# DumbBadgeFusion.net
KiCad netlist of a schematic drawn in EAGLE
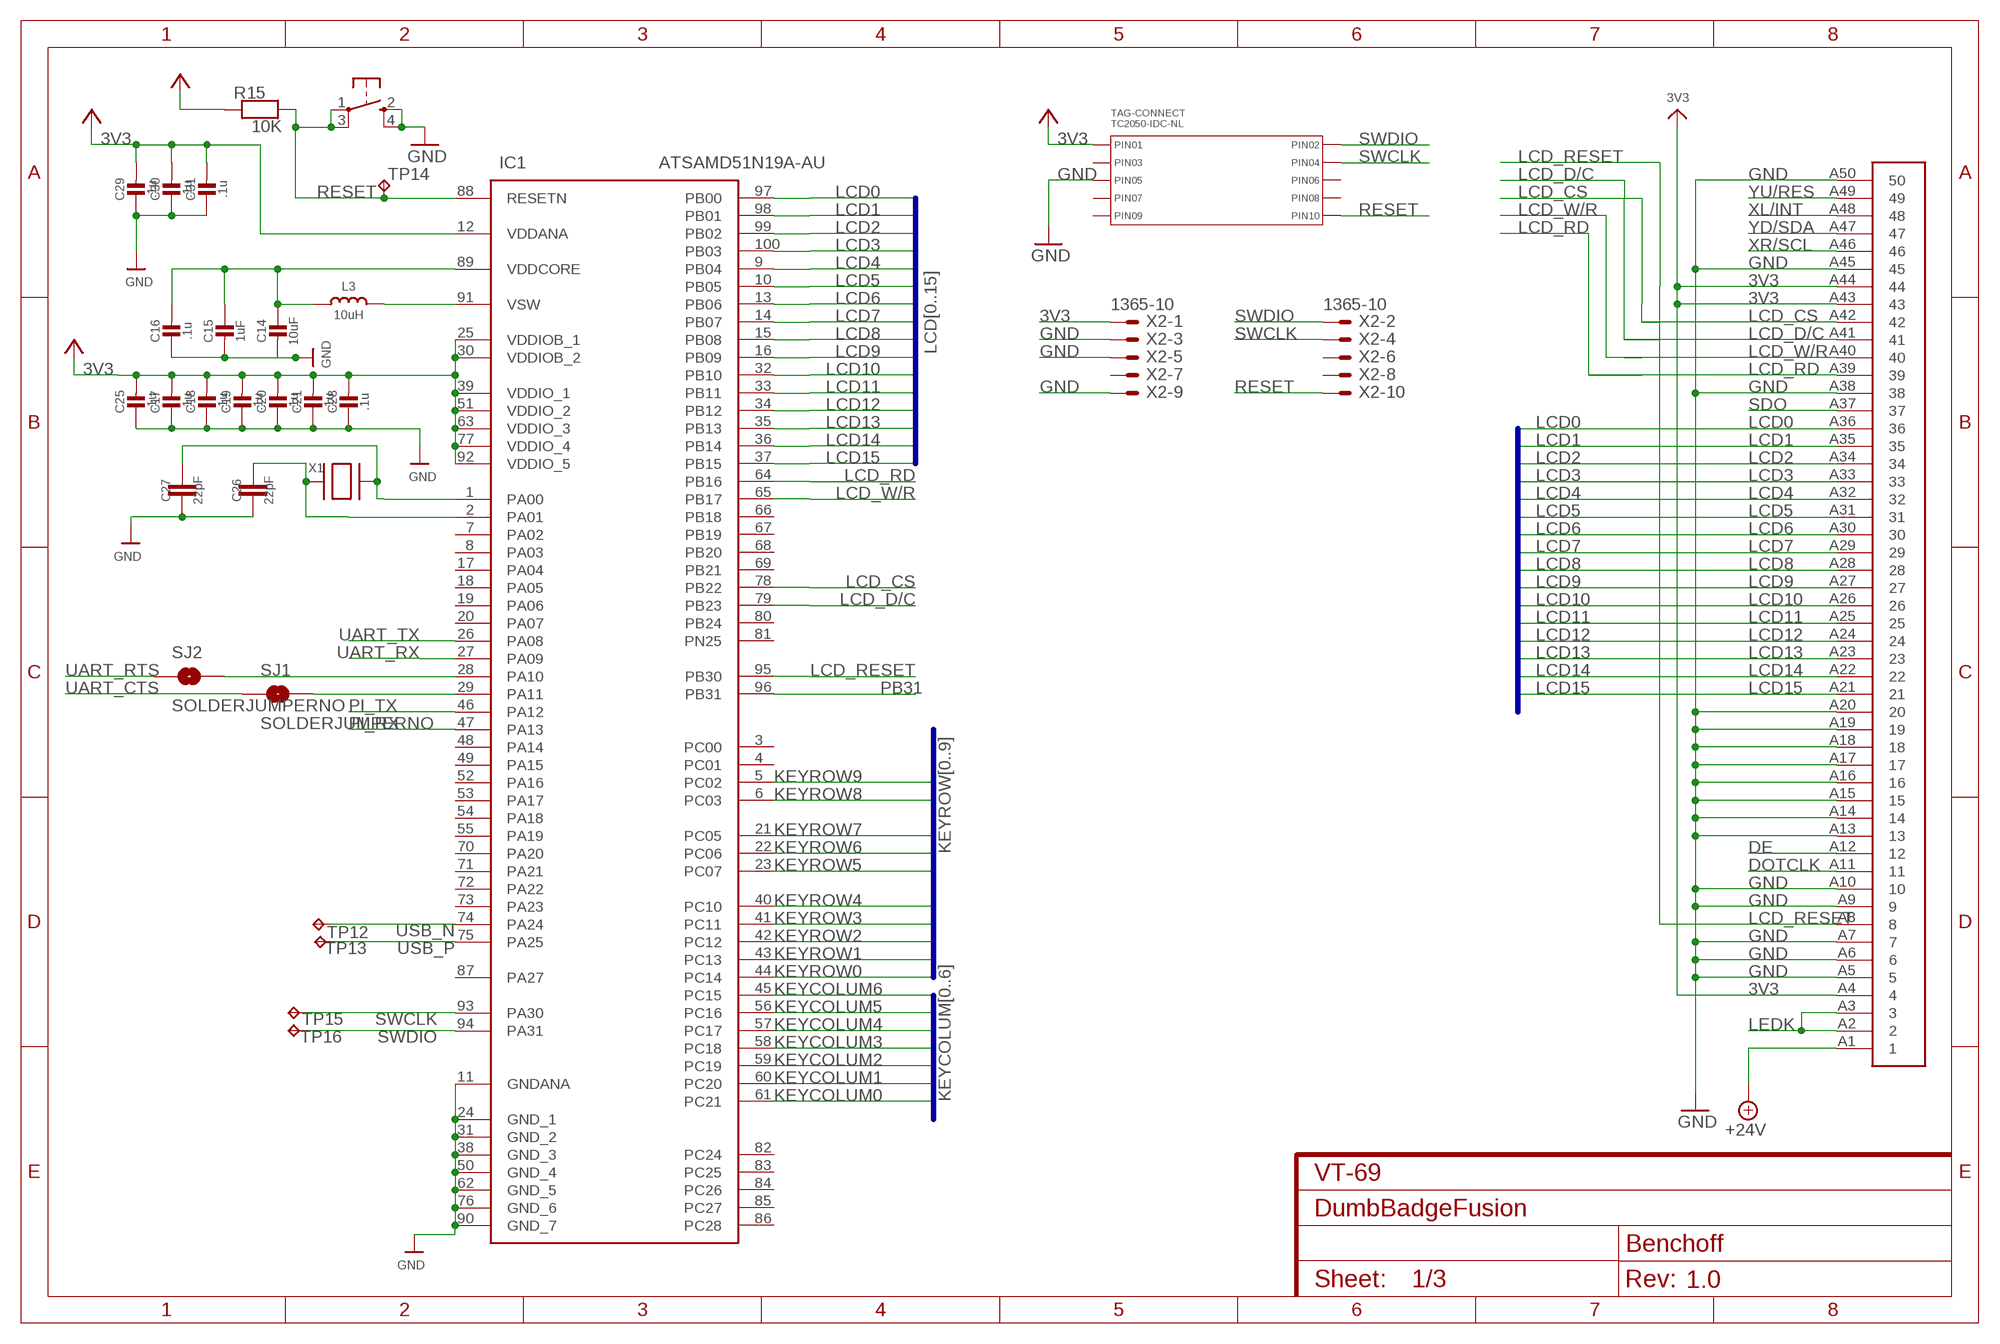
[diagram p0: schematic, sheet 1]
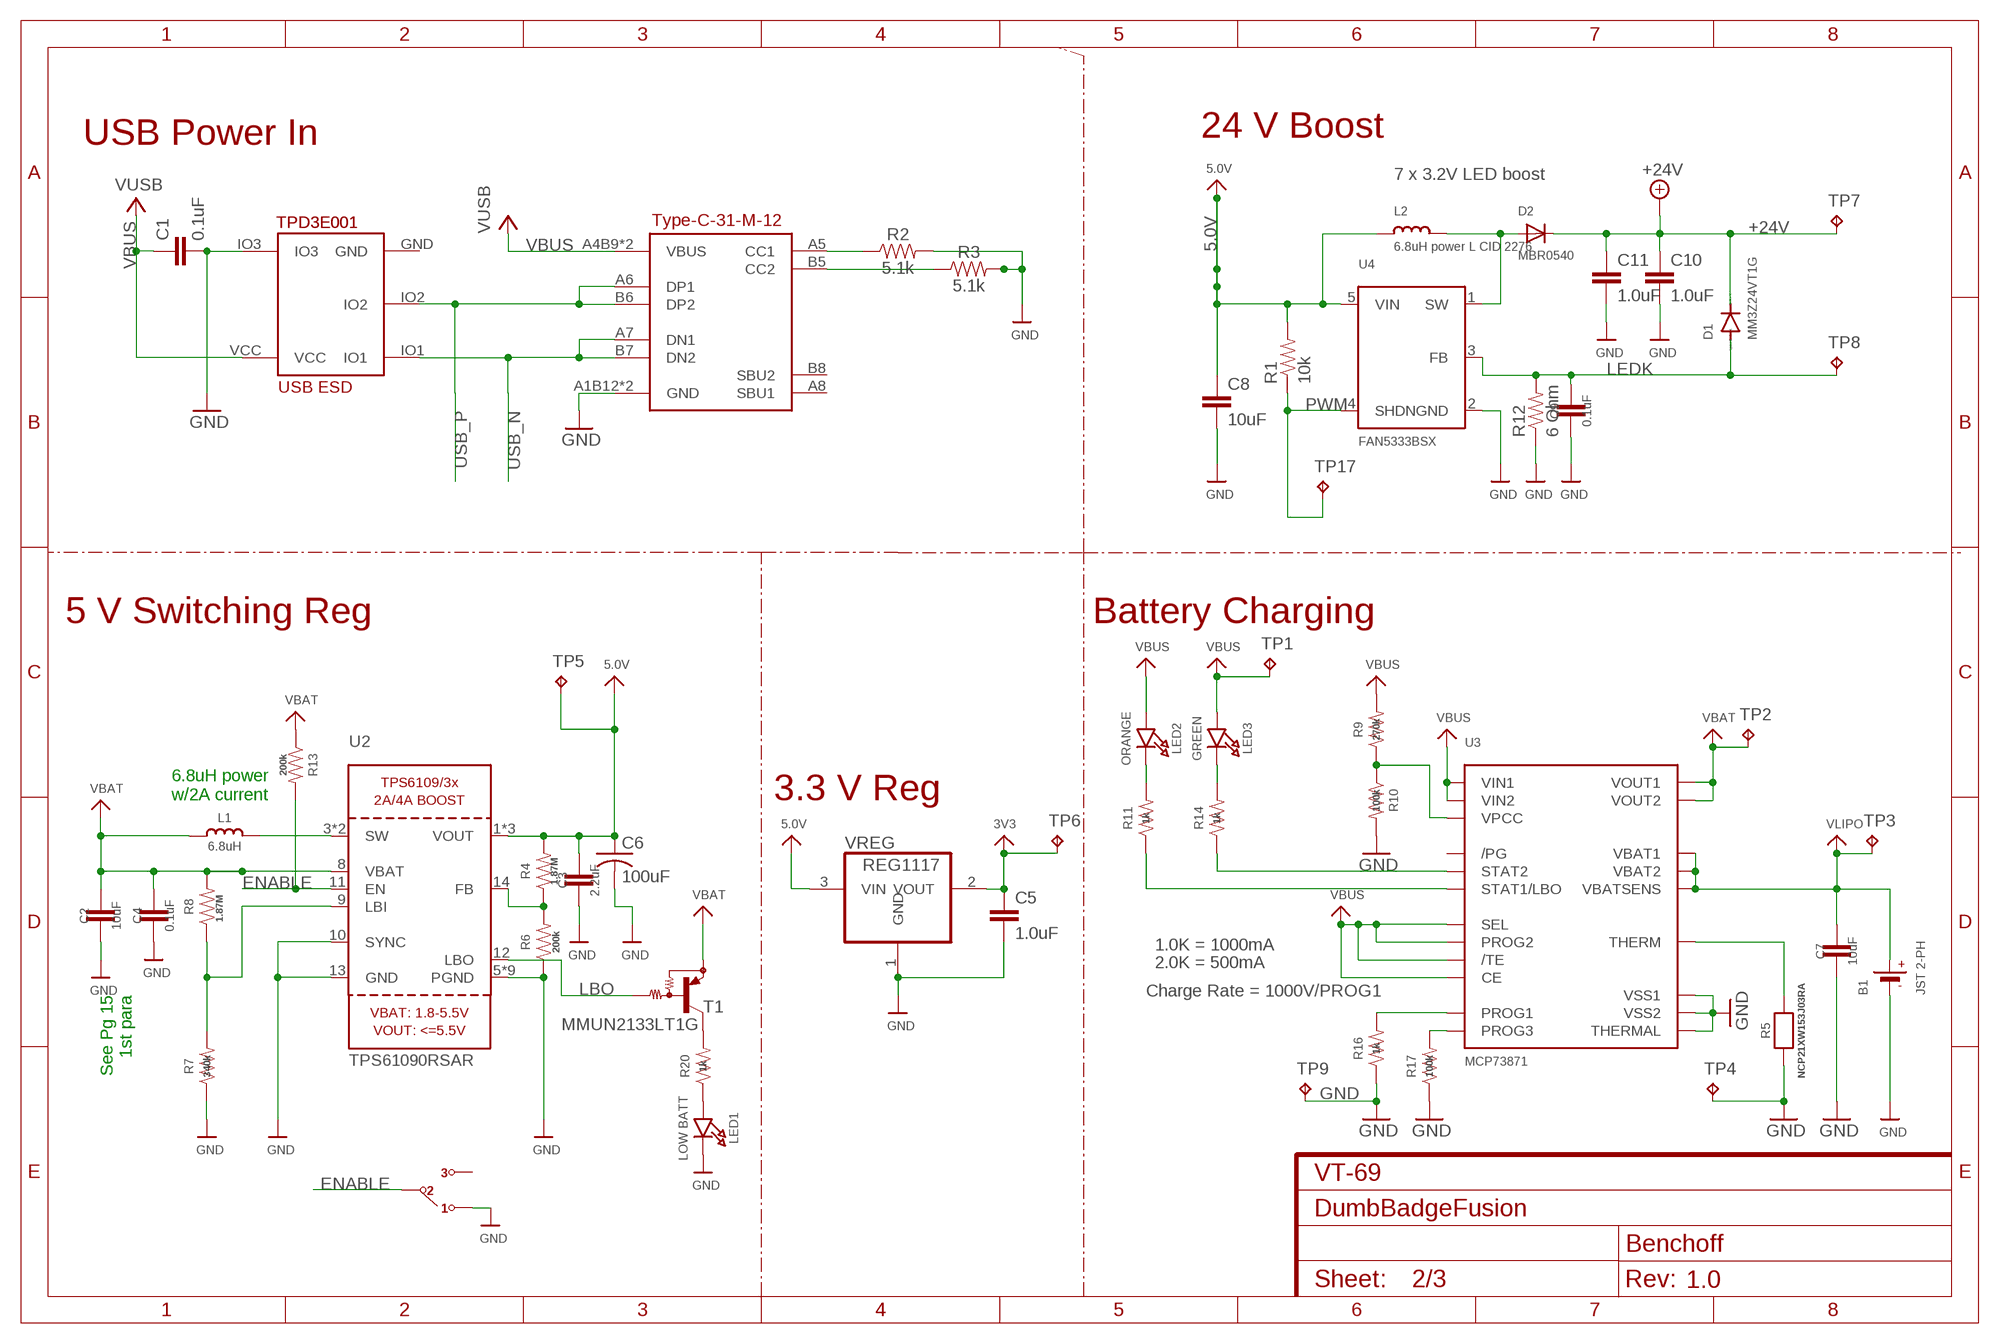
[diagram p1: schematic, sheet 2]
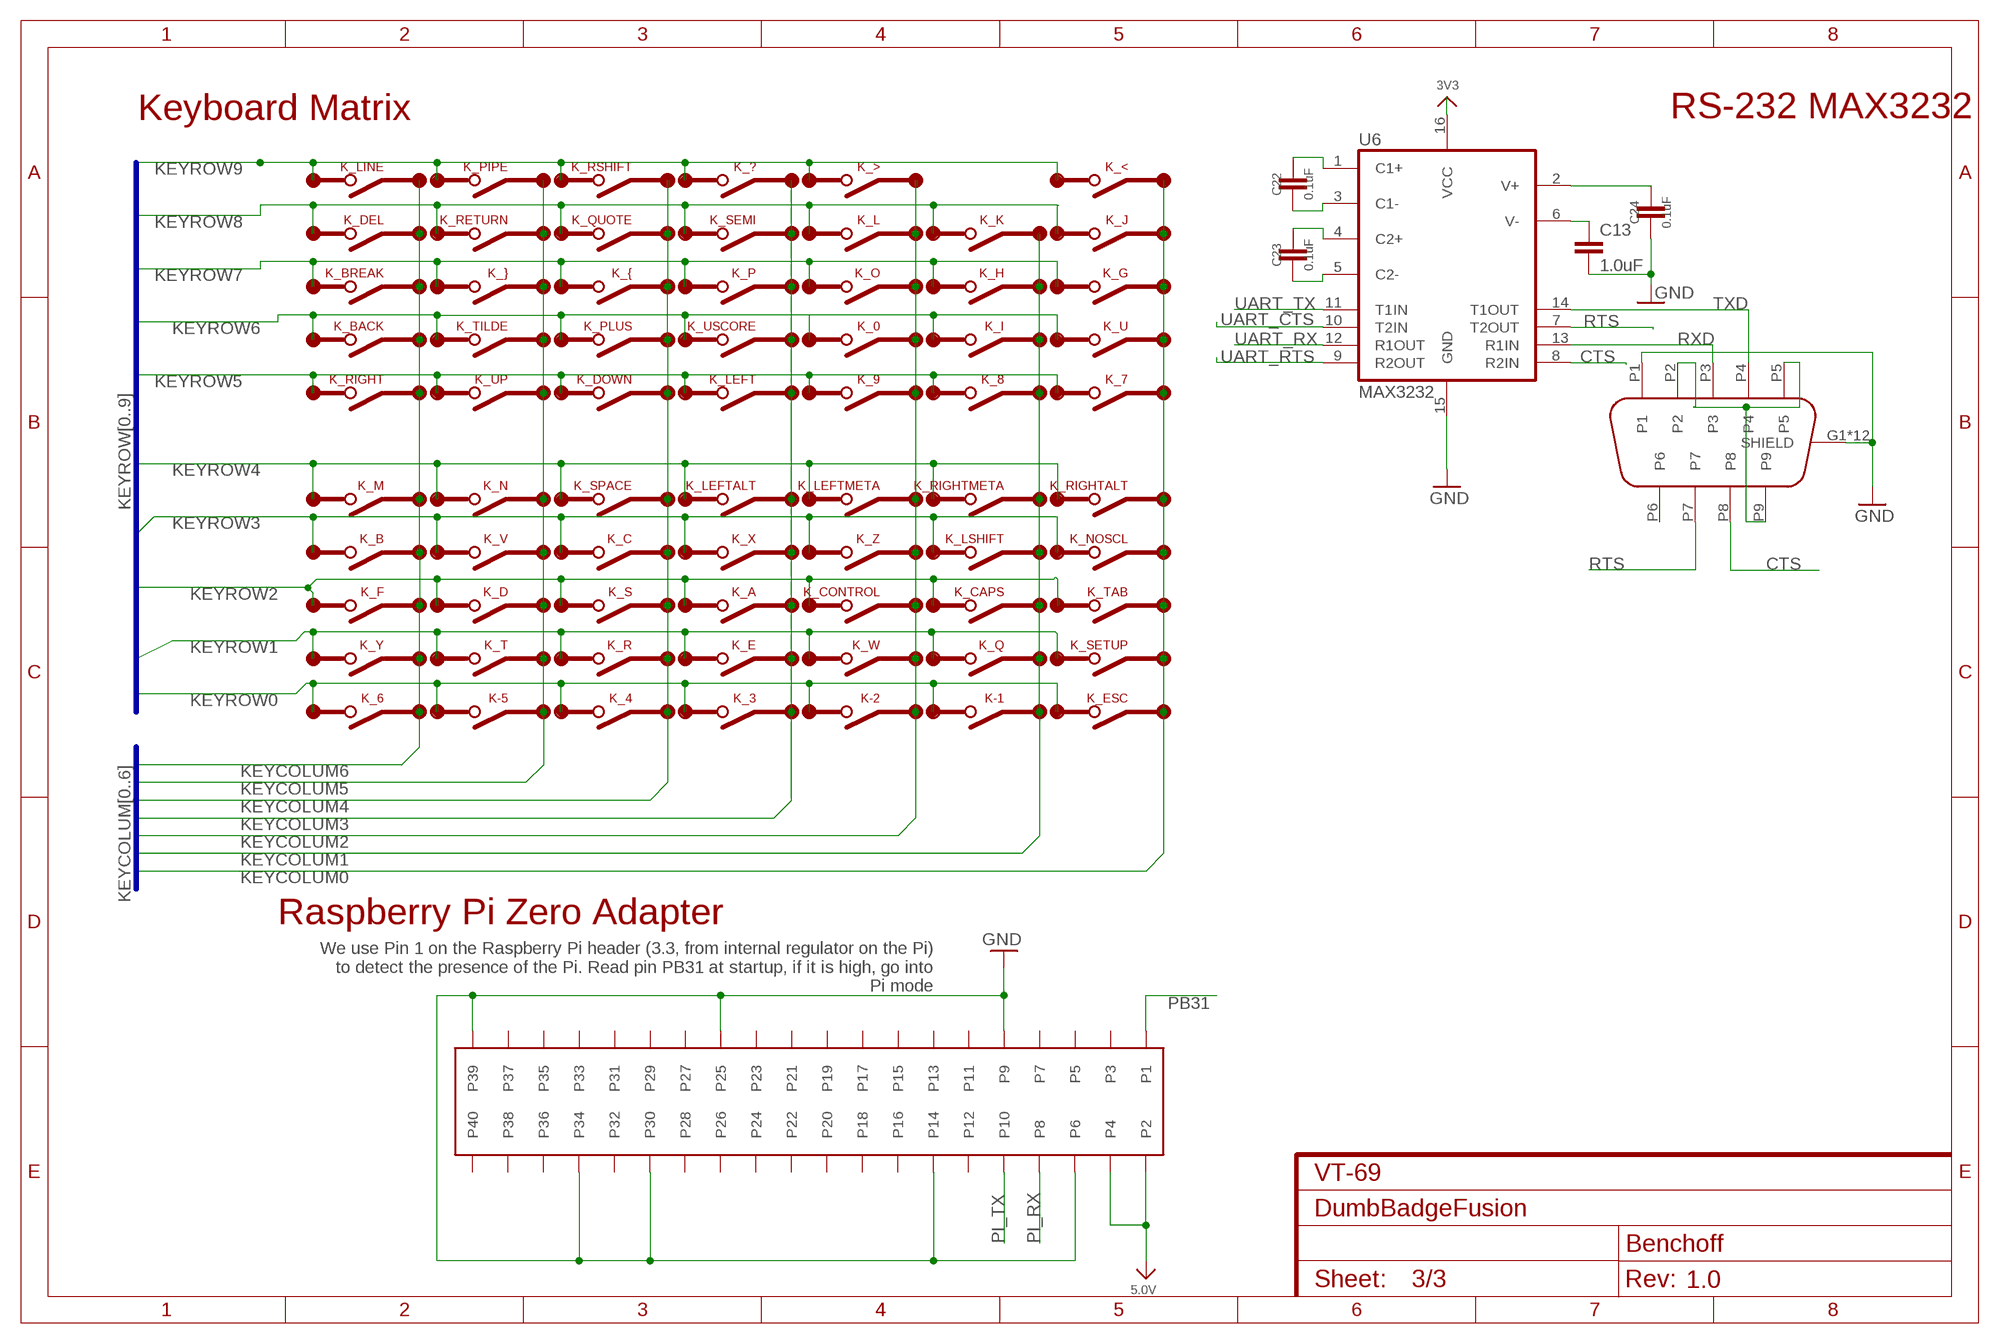
[diagram p2: schematic, sheet 3]

(export (version "E")
  (design (tool "Eeschema 10.0.6"))
  (components
    (comp (ref "C14")
      (value "10uF")
      (footprint "eagle-import:0805-NO")
      (libsource (lib "eagle-import") (part "CAP_CERAMIC0805-NOOUTLINE"))
    )
    (comp (ref "C15")
      (value "1uF")
      (footprint "eagle-import:0603-NO")
      (libsource (lib "eagle-import") (part "CAP_CERAMIC0603_NO"))
    )
    (comp (ref "C16")
      (value ".1u")
      (footprint "eagle-import:0603-NO")
      (libsource (lib "eagle-import") (part "CAP_CERAMIC0603_NO"))
    )
    (comp (ref "C17")
      (value ".1u")
      (footprint "eagle-import:0603-NO")
      (libsource (lib "eagle-import") (part "CAP_CERAMIC0603_NO"))
    )
    (comp (ref "C18")
      (value ".1u")
      (footprint "eagle-import:0603-NO")
      (libsource (lib "eagle-import") (part "CAP_CERAMIC0603_NO"))
    )
    (comp (ref "C19")
      (value ".1u")
      (footprint "eagle-import:0603-NO")
      (libsource (lib "eagle-import") (part "CAP_CERAMIC0603_NO"))
    )
    (comp (ref "C20")
      (value ".1u")
      (footprint "eagle-import:0603-NO")
      (libsource (lib "eagle-import") (part "CAP_CERAMIC0603_NO"))
    )
    (comp (ref "C21")
      (value ".1u")
      (footprint "eagle-import:0603-NO")
      (libsource (lib "eagle-import") (part "CAP_CERAMIC0603_NO"))
    )
    (comp (ref "C25")
      (value ".1u")
      (footprint "eagle-import:0603-NO")
      (libsource (lib "eagle-import") (part "CAP_CERAMIC0603_NO"))
    )
    (comp (ref "C26")
      (value "22pF")
      (footprint "eagle-import:0805")
      (libsource (lib "eagle-import") (part "1.0UF-0805-25V-10%"))
    )
    (comp (ref "C27")
      (value "22pF")
      (footprint "eagle-import:0805")
      (libsource (lib "eagle-import") (part "1.0UF-0805-25V-10%"))
    )
    (comp (ref "C28")
      (value ".1u")
      (footprint "eagle-import:0603-NO")
      (libsource (lib "eagle-import") (part "CAP_CERAMIC0603_NO"))
    )
    (comp (ref "C29")
      (value ".1u")
      (footprint "eagle-import:0603-NO")
      (libsource (lib "eagle-import") (part "CAP_CERAMIC0603_NO"))
    )
    (comp (ref "C30")
      (value ".1u")
      (footprint "eagle-import:0603-NO")
      (libsource (lib "eagle-import") (part "CAP_CERAMIC0603_NO"))
    )
    (comp (ref "C31")
      (value ".1u")
      (footprint "eagle-import:0603-NO")
      (libsource (lib "eagle-import") (part "CAP_CERAMIC0603_NO"))
    )
    (comp (ref "FPC50CONN")
      (value "50PINFPC")
      (footprint "eagle-import:62684-501100ALF")
      (libsource (lib "eagle-import") (part "50PINFPC"))
    )
    (comp (ref "IC1")
      (value "ATSAMD51N19A-AU")
      (footprint "eagle-import:QFP50P1600X1600X120-100N")
      (fields (field (name "MOUSER_PART_NUMBER") "556-ATSAMD51N19AAU"))
      (libsource (lib "eagle-import") (part "ATSAMD51N19A-AU"))
    )
    (comp (ref "L3")
      (value "10uH")
      (footprint "eagle-import:INDUCTOR_1007")
      (libsource (lib "eagle-import") (part "INDUCTOR"))
    )
    (comp (ref "R15")
      (value "10K")
      (footprint "eagle-import:0603-NO")
      (libsource (lib "eagle-import") (part "RESISTOR_0603_NOOUT"))
    )
    (comp (ref "SJ1")
      (value "SOLDERJUMPERNO")
      (footprint "eagle-import:SJ_2S-NO")
      (libsource (lib "eagle-import") (part "SOLDERJUMPERNO"))
    )
    (comp (ref "SJ2")
      (value "SOLDERJUMPERNO")
      (footprint "eagle-import:SJ_2S-NO")
      (libsource (lib "eagle-import") (part "SOLDERJUMPERNO"))
    )
    (comp (ref "SW1")
      (value "SPST_TACT-KMR2")
      (footprint "eagle-import:KMR2")
      (libsource (lib "eagle-import") (part "SPST_TACT-KMR2"))
    )
    (comp (ref "TAG-CONNECT")
      (value "TC2050-IDC-NL")
      (footprint "eagle-import:TC2050-IDC-NL")
      (fields (field (name "HOUSEPART") "NO"))
      (libsource (lib "eagle-import") (part "CON_02X05_TC2050-IDC-NL"))
    )
    (comp (ref "TP12")
      (value "TPB1,27")
      (footprint "eagle-import:B1,27")
      (libsource (lib "eagle-import") (part "TPB1,27"))
    )
    (comp (ref "TP13")
      (value "TPB1,27")
      (footprint "eagle-import:B1,27")
      (libsource (lib "eagle-import") (part "TPB1,27"))
    )
    (comp (ref "TP14")
      (value "TPB1,27")
      (footprint "eagle-import:B1,27")
      (libsource (lib "eagle-import") (part "TPB1,27"))
    )
    (comp (ref "TP15")
      (value "TPB1,27")
      (footprint "eagle-import:B1,27")
      (libsource (lib "eagle-import") (part "TPB1,27"))
    )
    (comp (ref "TP16")
      (value "TPB1,27")
      (footprint "eagle-import:B1,27")
      (libsource (lib "eagle-import") (part "TPB1,27"))
    )
    (comp (ref "X1")
      (value "NX3215SA-32.768K-STD-MUA-8")
      (footprint "eagle-import:XTAL3215")
      (libsource (lib "eagle-import") (part "XTAL-3.2X1.5"))
    )
    (comp (ref "X2")
      (value "1365-10")
      (footprint "eagle-import:1365-10")
      (libsource (lib "eagle-import") (part "1365-10"))
    )
    (comp (ref "B1")
      (value "JST 2-PH")
      (footprint "eagle-import:JSTPH2")
      (libsource (lib "eagle-import") (part "BATTERY"))
    )
    (comp (ref "C1")
      (value "0.1uF")
      (footprint "eagle-import:0805")
      (libsource (lib "eagle-import") (part "1.0UF-0805-25V-10%"))
    )
    (comp (ref "C2")
      (value "10uF")
      (footprint "eagle-import:0805")
      (libsource (lib "eagle-import") (part "1.0UF-0805-25V-10%"))
    )
    (comp (ref "C3")
      (value "2.2uF")
      (footprint "eagle-import:0805")
      (libsource (lib "eagle-import") (part "1.0UF-0805-25V-10%"))
    )
    (comp (ref "C4")
      (value "0.1uF")
      (footprint "eagle-import:0805")
      (libsource (lib "eagle-import") (part "1.0UF-0805-25V-10%"))
    )
    (comp (ref "C5")
      (value "1.0uF")
      (footprint "eagle-import:0805")
      (libsource (lib "eagle-import") (part "1.0UF-0805-25V-10%"))
    )
    (comp (ref "C6")
      (value "100uF")
      (footprint "eagle-import:C1210")
      (libsource (lib "eagle-import") (part "C-USC1210"))
    )
    (comp (ref "C7")
      (value "10uF")
      (footprint "eagle-import:0805")
      (libsource (lib "eagle-import") (part "1.0UF-0805-25V-10%"))
    )
    (comp (ref "C8")
      (value "10uF")
      (footprint "eagle-import:0805")
      (libsource (lib "eagle-import") (part "1.0UF-0805-25V-10%"))
    )
    (comp (ref "C9")
      (value "0.1uF")
      (footprint "eagle-import:0805")
      (libsource (lib "eagle-import") (part "1.0UF-0805-25V-10%"))
    )
    (comp (ref "C10")
      (value "1.0uF")
      (footprint "eagle-import:0805")
      (libsource (lib "eagle-import") (part "1.0UF-0805-25V-10%"))
    )
    (comp (ref "C11")
      (value "1.0uF")
      (footprint "eagle-import:0805")
      (libsource (lib "eagle-import") (part "1.0UF-0805-25V-10%"))
    )
    (comp (ref "D1")
      (value "MM3Z24VT1G")
      (footprint "eagle-import:SOD323-W")
      (libsource (lib "eagle-import") (part "DIODE-SOD323-W"))
    )
    (comp (ref "D2")
      (value "MBR0540")
      (footprint "eagle-import:SOD-123")
      (libsource (lib "eagle-import") (part "DIODESOD-123"))
    )
    (comp (ref "L1")
      (value "6.8uH")
      (footprint "eagle-import:INDUCTOR_5X5MM_TDK_VLC5045")
      (libsource (lib "eagle-import") (part "INDUCTORTDK_VLC5045"))
    )
    (comp (ref "L2")
      (value "6.8uH power L CID 2276")
      (footprint "eagle-import:INDUCTOR_5X5MM_NR5040_NOTHERMALS")
      (libsource (lib "eagle-import") (part "INDUCTORNR5040"))
    )
    (comp (ref "LED1")
      (value "LOW BATT")
      (footprint "eagle-import:CHIPLED_0805_NOOUTLINE")
      (libsource (lib "eagle-import") (part "LED0805_NOOUTLINE"))
    )
    (comp (ref "LED2")
      (value "ORANGE")
      (footprint "eagle-import:CHIPLED_0805_NOOUTLINE")
      (libsource (lib "eagle-import") (part "LED0805_NOOUTLINE"))
    )
    (comp (ref "LED3")
      (value "GREEN")
      (footprint "eagle-import:CHIPLED_0805_NOOUTLINE")
      (libsource (lib "eagle-import") (part "LED0805_NOOUTLINE"))
    )
    (comp (ref "R1")
      (value "10k")
      (footprint "eagle-import:0603")
      (libsource (lib "eagle-import") (part "1KOHM-0603-1/10W-1%"))
    )
    (comp (ref "R2")
      (value "5.1k")
      (footprint "eagle-import:0603")
      (libsource (lib "eagle-import") (part "1KOHM-0603-1/10W-1%"))
    )
    (comp (ref "R3")
      (value "5.1k")
      (footprint "eagle-import:0603")
      (libsource (lib "eagle-import") (part "1KOHM-0603-1/10W-1%"))
    )
    (comp (ref "R4")
      (value "1.87M")
      (footprint "eagle-import:0603")
      (libsource (lib "eagle-import") (part "1KOHM-0603-1/10W-1%"))
    )
    (comp (ref "R5")
      (value "NCP21XW153J03RA")
      (footprint "eagle-import:0805-NO")
      (libsource (lib "eagle-import") (part "RESISTOR0805_NOOUTLINE"))
    )
    (comp (ref "R6")
      (value "200k")
      (footprint "eagle-import:0603")
      (libsource (lib "eagle-import") (part "1KOHM-0603-1/10W-1%"))
    )
    (comp (ref "R7")
      (value "340k")
      (footprint "eagle-import:0603")
      (libsource (lib "eagle-import") (part "1KOHM-0603-1/10W-1%"))
    )
    (comp (ref "R8")
      (value "1.87M")
      (footprint "eagle-import:0603")
      (libsource (lib "eagle-import") (part "1KOHM-0603-1/10W-1%"))
    )
    (comp (ref "R9")
      (value "270k")
      (footprint "eagle-import:0603")
      (libsource (lib "eagle-import") (part "1KOHM-0603-1/10W-1%"))
    )
    (comp (ref "R10")
      (value "100k")
      (footprint "eagle-import:0603")
      (libsource (lib "eagle-import") (part "1KOHM-0603-1/10W-1%"))
    )
    (comp (ref "R11")
      (value "1k")
      (footprint "eagle-import:0603")
      (libsource (lib "eagle-import") (part "1KOHM-0603-1/10W-1%"))
    )
    (comp (ref "R12")
      (value "6 Ohm")
      (footprint "eagle-import:0603")
      (libsource (lib "eagle-import") (part "1KOHM-0603-1/10W-1%"))
    )
    (comp (ref "R13")
      (value "200k")
      (footprint "eagle-import:0603")
      (libsource (lib "eagle-import") (part "1KOHM-0603-1/10W-1%"))
    )
    (comp (ref "R14")
      (value "1k")
      (footprint "eagle-import:0603")
      (libsource (lib "eagle-import") (part "1KOHM-0603-1/10W-1%"))
    )
    (comp (ref "R16")
      (value "1k")
      (footprint "eagle-import:0603")
      (libsource (lib "eagle-import") (part "1KOHM-0603-1/10W-1%"))
    )
    (comp (ref "R17")
      (value "100k")
      (footprint "eagle-import:0603")
      (libsource (lib "eagle-import") (part "1KOHM-0603-1/10W-1%"))
    )
    (comp (ref "R20")
      (value "1k")
      (footprint "eagle-import:0603")
      (libsource (lib "eagle-import") (part "1KOHM-0603-1/10W-1%"))
    )
    (comp (ref "T1")
      (value "MMUN2133LT1G")
      (footprint "eagle-import:SC59-BEC")
      (libsource (lib "eagle-import") (part "-PNP_DRIVER-SC59-BECMUN2114T1"))
    )
    (comp (ref "TP1")
      (value "TPB1,27")
      (footprint "eagle-import:B1,27")
      (libsource (lib "eagle-import") (part "TPB1,27"))
    )
    (comp (ref "TP2")
      (value "TPB1,27")
      (footprint "eagle-import:B1,27")
      (libsource (lib "eagle-import") (part "TPB1,27"))
    )
    (comp (ref "TP3")
      (value "TPB1,27")
      (footprint "eagle-import:B1,27")
      (libsource (lib "eagle-import") (part "TPB1,27"))
    )
    (comp (ref "TP4")
      (value "TPB1,27")
      (footprint "eagle-import:B1,27")
      (libsource (lib "eagle-import") (part "TPB1,27"))
    )
    (comp (ref "TP5")
      (value "TPB1,27")
      (footprint "eagle-import:B1,27")
      (libsource (lib "eagle-import") (part "TPB1,27"))
    )
    (comp (ref "TP6")
      (value "TPB1,27")
      (footprint "eagle-import:B1,27")
      (libsource (lib "eagle-import") (part "TPB1,27"))
    )
    (comp (ref "TP7")
      (value "TPB1,27")
      (footprint "eagle-import:B1,27")
      (libsource (lib "eagle-import") (part "TPB1,27"))
    )
    (comp (ref "TP8")
      (value "TPB1,27")
      (footprint "eagle-import:B1,27")
      (libsource (lib "eagle-import") (part "TPB1,27"))
    )
    (comp (ref "TP9")
      (value "TPB1,27")
      (footprint "eagle-import:B1,27")
      (libsource (lib "eagle-import") (part "TPB1,27"))
    )
    (comp (ref "TP17")
      (value "TPB1,27")
      (footprint "eagle-import:B1,27")
      (libsource (lib "eagle-import") (part "TPB1,27"))
    )
    (comp (ref "U$5")
      (value "OS102011MA1QN1")
      (footprint "eagle-import:OS102011MA1QN1")
      (libsource (lib "eagle-import") (part "OS102011MA1QN1"))
    )
    (comp (ref "U2")
      (value "TPS61090RSAR")
      (footprint "eagle-import:PVQFN-16")
      (libsource (lib "eagle-import") (part "VREG_TPS6103X"))
    )
    (comp (ref "U3")
      (value "MCP73871")
      (footprint "eagle-import:QFN20_4MM")
      (libsource (lib "eagle-import") (part "MCP73871"))
    )
    (comp (ref "U4")
      (value "FAN5333BSX")
      (footprint "eagle-import:SOT23-5@1")
      (libsource (lib "eagle-import") (part "FAN5331"))
    )
    (comp (ref "U5")
      (value "TPD3E001SOT5")
      (footprint "eagle-import:SOT(5)")
      (libsource (lib "eagle-import") (part "TPD3E001SOT5"))
    )
    (comp (ref "USB")
      (value "TYPE-C-31-M-12")
      (footprint "eagle-import:TYPE-C-31-M-12")
      (libsource (lib "eagle-import") (part "TYPE-C-31-M-12"))
    )
    (comp (ref "VREG")
      (value "REG1117")
      (footprint "eagle-import:SOT223")
      (libsource (lib "eagle-import") (part "REG1117"))
    )
    (comp (ref "C13")
      (value "1.0uF")
      (footprint "eagle-import:0805")
      (libsource (lib "eagle-import") (part "1.0UF-0805-25V-10%"))
    )
    (comp (ref "C22")
      (value "0.1uF")
      (footprint "eagle-import:0805")
      (libsource (lib "eagle-import") (part "1.0UF-0805-25V-10%"))
    )
    (comp (ref "C23")
      (value "0.1uF")
      (footprint "eagle-import:0805")
      (libsource (lib "eagle-import") (part "1.0UF-0805-25V-10%"))
    )
    (comp (ref "C24")
      (value "0.1uF")
      (footprint "eagle-import:0805")
      (libsource (lib "eagle-import") (part "1.0UF-0805-25V-10%"))
    )
    (comp (ref "DE9FEMALE")
      (value "EDGEMOUNTDE9")
      (footprint "eagle-import:DE09S065TLF")
      (libsource (lib "eagle-import") (part "EDGEMOUNTDE9"))
    )
    (comp (ref "K-1")
      (value "1U_PAD")
      (footprint "eagle-import:SILICONE_SWITCH")
      (libsource (lib "eagle-import") (part "1U_PAD"))
    )
    (comp (ref "K-2")
      (value "1U_PAD")
      (footprint "eagle-import:SILICONE_SWITCH")
      (libsource (lib "eagle-import") (part "1U_PAD"))
    )
    (comp (ref "K-5")
      (value "1U_PAD")
      (footprint "eagle-import:SILICONE_SWITCH")
      (libsource (lib "eagle-import") (part "1U_PAD"))
    )
    (comp (ref "K_0")
      (value "1U_PAD")
      (footprint "eagle-import:SILICONE_SWITCH")
      (libsource (lib "eagle-import") (part "1U_PAD"))
    )
    (comp (ref "K_3")
      (value "1U_PAD")
      (footprint "eagle-import:SILICONE_SWITCH")
      (libsource (lib "eagle-import") (part "1U_PAD"))
    )
    (comp (ref "K_4")
      (value "1U_PAD")
      (footprint "eagle-import:SILICONE_SWITCH")
      (libsource (lib "eagle-import") (part "1U_PAD"))
    )
    (comp (ref "K_6")
      (value "1U_PAD")
      (footprint "eagle-import:SILICONE_SWITCH")
      (libsource (lib "eagle-import") (part "1U_PAD"))
    )
    (comp (ref "K_7")
      (value "1U_PAD")
      (footprint "eagle-import:SILICONE_SWITCH")
      (libsource (lib "eagle-import") (part "1U_PAD"))
    )
    (comp (ref "K_8")
      (value "1U_PAD")
      (footprint "eagle-import:SILICONE_SWITCH")
      (libsource (lib "eagle-import") (part "1U_PAD"))
    )
    (comp (ref "K_9")
      (value "1U_PAD")
      (footprint "eagle-import:SILICONE_SWITCH")
      (libsource (lib "eagle-import") (part "1U_PAD"))
    )
    (comp (ref "K_<")
      (value "1U_PAD")
      (footprint "eagle-import:SILICONE_SWITCH")
      (libsource (lib "eagle-import") (part "1U_PAD"))
    )
    (comp (ref "K_>")
      (value "1U_PAD")
      (footprint "eagle-import:SILICONE_SWITCH")
      (libsource (lib "eagle-import") (part "1U_PAD"))
    )
    (comp (ref "K_?")
      (value "1U_PAD")
      (footprint "eagle-import:SILICONE_SWITCH")
      (libsource (lib "eagle-import") (part "1U_PAD"))
    )
    (comp (ref "K_A")
      (value "1U_PAD")
      (footprint "eagle-import:SILICONE_SWITCH")
      (libsource (lib "eagle-import") (part "1U_PAD"))
    )
    (comp (ref "K_B")
      (value "1U_PAD")
      (footprint "eagle-import:SILICONE_SWITCH")
      (libsource (lib "eagle-import") (part "1U_PAD"))
    )
    (comp (ref "K_BACK")
      (value "1U_PAD")
      (footprint "eagle-import:SILICONE_SWITCH")
      (libsource (lib "eagle-import") (part "1U_PAD"))
    )
    (comp (ref "K_BREAK")
      (value "1U_PAD")
      (footprint "eagle-import:SILICONE_SWITCH")
      (libsource (lib "eagle-import") (part "1U_PAD"))
    )
    (comp (ref "K_C")
      (value "1U_PAD")
      (footprint "eagle-import:SILICONE_SWITCH")
      (libsource (lib "eagle-import") (part "1U_PAD"))
    )
    (comp (ref "K_CAPS")
      (value "1U_PAD")
      (footprint "eagle-import:SILICONE_SWITCH")
      (libsource (lib "eagle-import") (part "1U_PAD"))
    )
    (comp (ref "K_CONTROL")
      (value "2U_PAD")
      (footprint "eagle-import:SILICONE_SWITCH_2U")
      (libsource (lib "eagle-import") (part "2U_PAD"))
    )
    (comp (ref "K_D")
      (value "1U_PAD")
      (footprint "eagle-import:SILICONE_SWITCH")
      (libsource (lib "eagle-import") (part "1U_PAD"))
    )
    (comp (ref "K_DEL")
      (value "1U_PAD")
      (footprint "eagle-import:SILICONE_SWITCH")
      (libsource (lib "eagle-import") (part "1U_PAD"))
    )
    (comp (ref "K_DOWN")
      (value "1U_PAD")
      (footprint "eagle-import:SILICONE_SWITCH")
      (libsource (lib "eagle-import") (part "1U_PAD"))
    )
    (comp (ref "K_E")
      (value "1U_PAD")
      (footprint "eagle-import:SILICONE_SWITCH")
      (libsource (lib "eagle-import") (part "1U_PAD"))
    )
    (comp (ref "K_ESC")
      (value "1U_PAD")
      (footprint "eagle-import:SILICONE_SWITCH")
      (libsource (lib "eagle-import") (part "1U_PAD"))
    )
    (comp (ref "K_F")
      (value "1U_PAD")
      (footprint "eagle-import:SILICONE_SWITCH")
      (libsource (lib "eagle-import") (part "1U_PAD"))
    )
    (comp (ref "K_G")
      (value "1U_PAD")
      (footprint "eagle-import:SILICONE_SWITCH")
      (libsource (lib "eagle-import") (part "1U_PAD"))
    )
    (comp (ref "K_H")
      (value "1U_PAD")
      (footprint "eagle-import:SILICONE_SWITCH")
      (libsource (lib "eagle-import") (part "1U_PAD"))
    )
    (comp (ref "K_I")
      (value "1U_PAD")
      (footprint "eagle-import:SILICONE_SWITCH")
      (libsource (lib "eagle-import") (part "1U_PAD"))
    )
    (comp (ref "K_J")
      (value "1U_PAD")
      (footprint "eagle-import:SILICONE_SWITCH")
      (libsource (lib "eagle-import") (part "1U_PAD"))
    )
    (comp (ref "K_K")
      (value "1U_PAD")
      (footprint "eagle-import:SILICONE_SWITCH")
      (libsource (lib "eagle-import") (part "1U_PAD"))
    )
    (comp (ref "K_L")
      (value "1U_PAD")
      (footprint "eagle-import:SILICONE_SWITCH")
      (libsource (lib "eagle-import") (part "1U_PAD"))
    )
    (comp (ref "K_LEFT")
      (value "1U_PAD")
      (footprint "eagle-import:SILICONE_SWITCH")
      (libsource (lib "eagle-import") (part "1U_PAD"))
    )
    (comp (ref "K_LEFTALT")
      (value "1U_PAD")
      (footprint "eagle-import:SILICONE_SWITCH")
      (libsource (lib "eagle-import") (part "1U_PAD"))
    )
    (comp (ref "K_LEFTMETA")
      (value "1U_PAD")
      (footprint "eagle-import:SILICONE_SWITCH")
      (libsource (lib "eagle-import") (part "1U_PAD"))
    )
    (comp (ref "K_LINE")
      (value "1U_PAD")
      (footprint "eagle-import:SILICONE_SWITCH")
      (libsource (lib "eagle-import") (part "1U_PAD"))
    )
    (comp (ref "K_LSHIFT")
      (value "2U_PAD")
      (footprint "eagle-import:SILICONE_SWITCH_2U")
      (libsource (lib "eagle-import") (part "2U_PAD"))
    )
    (comp (ref "K_M")
      (value "1U_PAD")
      (footprint "eagle-import:SILICONE_SWITCH")
      (libsource (lib "eagle-import") (part "1U_PAD"))
    )
    (comp (ref "K_N")
      (value "1U_PAD")
      (footprint "eagle-import:SILICONE_SWITCH")
      (libsource (lib "eagle-import") (part "1U_PAD"))
    )
    (comp (ref "K_NOSCL")
      (value "1U_PAD")
      (footprint "eagle-import:SILICONE_SWITCH")
      (libsource (lib "eagle-import") (part "1U_PAD"))
    )
    (comp (ref "K_O")
      (value "1U_PAD")
      (footprint "eagle-import:SILICONE_SWITCH")
      (libsource (lib "eagle-import") (part "1U_PAD"))
    )
    (comp (ref "K_P")
      (value "1U_PAD")
      (footprint "eagle-import:SILICONE_SWITCH")
      (libsource (lib "eagle-import") (part "1U_PAD"))
    )
    (comp (ref "K_PIPE")
      (value "1U_PAD")
      (footprint "eagle-import:SILICONE_SWITCH")
      (libsource (lib "eagle-import") (part "1U_PAD"))
    )
    (comp (ref "K_PLUS")
      (value "1U_PAD")
      (footprint "eagle-import:SILICONE_SWITCH")
      (libsource (lib "eagle-import") (part "1U_PAD"))
    )
    (comp (ref "K_Q")
      (value "1U_PAD")
      (footprint "eagle-import:SILICONE_SWITCH")
      (libsource (lib "eagle-import") (part "1U_PAD"))
    )
    (comp (ref "K_QUOTE")
      (value "1U_PAD")
      (footprint "eagle-import:SILICONE_SWITCH")
      (libsource (lib "eagle-import") (part "1U_PAD"))
    )
    (comp (ref "K_R")
      (value "1U_PAD")
      (footprint "eagle-import:SILICONE_SWITCH")
      (libsource (lib "eagle-import") (part "1U_PAD"))
    )
    (comp (ref "K_RETURN")
      (value "RETURN_PAD")
      (footprint "eagle-import:SILICONE_RETURN")
      (libsource (lib "eagle-import") (part "RETURN_PAD"))
    )
    (comp (ref "K_RIGHT")
      (value "1U_PAD")
      (footprint "eagle-import:SILICONE_SWITCH")
      (libsource (lib "eagle-import") (part "1U_PAD"))
    )
    (comp (ref "K_RIGHTALT")
      (value "1U_PAD")
      (footprint "eagle-import:SILICONE_SWITCH")
      (libsource (lib "eagle-import") (part "1U_PAD"))
    )
    (comp (ref "K_RIGHTMETA")
      (value "1U_PAD")
      (footprint "eagle-import:SILICONE_SWITCH")
      (libsource (lib "eagle-import") (part "1U_PAD"))
    )
    (comp (ref "K_RSHIFT")
      (value "2U_PAD")
      (footprint "eagle-import:SILICONE_SWITCH_2U")
      (libsource (lib "eagle-import") (part "2U_PAD"))
    )
    (comp (ref "K_S")
      (value "1U_PAD")
      (footprint "eagle-import:SILICONE_SWITCH")
      (libsource (lib "eagle-import") (part "1U_PAD"))
    )
    (comp (ref "K_SEMI")
      (value "1U_PAD")
      (footprint "eagle-import:SILICONE_SWITCH")
      (libsource (lib "eagle-import") (part "1U_PAD"))
    )
    (comp (ref "K_SETUP")
      (value "2U_PAD")
      (footprint "eagle-import:SILICONE_SWITCH_2U")
      (libsource (lib "eagle-import") (part "2U_PAD"))
    )
    (comp (ref "K_SPACE")
      (value "SPACE_PAD")
      (footprint "eagle-import:SILICONE_SPACE")
      (libsource (lib "eagle-import") (part "SPACE_PAD"))
    )
    (comp (ref "K_T")
      (value "1U_PAD")
      (footprint "eagle-import:SILICONE_SWITCH")
      (libsource (lib "eagle-import") (part "1U_PAD"))
    )
    (comp (ref "K_TAB")
      (value "1U_PAD")
      (footprint "eagle-import:SILICONE_SWITCH")
      (libsource (lib "eagle-import") (part "1U_PAD"))
    )
    (comp (ref "K_TILDE")
      (value "1U_PAD")
      (footprint "eagle-import:SILICONE_SWITCH")
      (libsource (lib "eagle-import") (part "1U_PAD"))
    )
    (comp (ref "K_U")
      (value "1U_PAD")
      (footprint "eagle-import:SILICONE_SWITCH")
      (libsource (lib "eagle-import") (part "1U_PAD"))
    )
    (comp (ref "K_UP")
      (value "1U_PAD")
      (footprint "eagle-import:SILICONE_SWITCH")
      (libsource (lib "eagle-import") (part "1U_PAD"))
    )
    (comp (ref "K_USCORE")
      (value "1U_PAD")
      (footprint "eagle-import:SILICONE_SWITCH")
      (libsource (lib "eagle-import") (part "1U_PAD"))
    )
    (comp (ref "K_V")
      (value "1U_PAD")
      (footprint "eagle-import:SILICONE_SWITCH")
      (libsource (lib "eagle-import") (part "1U_PAD"))
    )
    (comp (ref "K_W")
      (value "1U_PAD")
      (footprint "eagle-import:SILICONE_SWITCH")
      (libsource (lib "eagle-import") (part "1U_PAD"))
    )
    (comp (ref "K_X")
      (value "1U_PAD")
      (footprint "eagle-import:SILICONE_SWITCH")
      (libsource (lib "eagle-import") (part "1U_PAD"))
    )
    (comp (ref "K_Y")
      (value "1U_PAD")
      (footprint "eagle-import:SILICONE_SWITCH")
      (libsource (lib "eagle-import") (part "1U_PAD"))
    )
    (comp (ref "K_Z")
      (value "1U_PAD")
      (footprint "eagle-import:SILICONE_SWITCH")
      (libsource (lib "eagle-import") (part "1U_PAD"))
    )
    (comp (ref "K_{")
      (value "1U_PAD")
      (footprint "eagle-import:SILICONE_SWITCH")
      (libsource (lib "eagle-import") (part "1U_PAD"))
    )
    (comp (ref "K_}")
      (value "1U_PAD")
      (footprint "eagle-import:SILICONE_SWITCH")
      (libsource (lib "eagle-import") (part "1U_PAD"))
    )
    (comp (ref "U$30")
      (value "SAMTEC_PI_REVERSE")
      (footprint "eagle-import:HLE-120-02-G-DV-BE-A--REVERSEMOUNT")
      (libsource (lib "eagle-import") (part "SAMTEC_PI_REVERSE"))
    )
    (comp (ref "U6")
      (value "MAX3232")
      (footprint "eagle-import:SO16")
      (libsource (lib "eagle-import") (part "MAX2323SOIC16"))
    )
  )
  (nets
    (net (code "1") (name "+24V") (class "Default")
      (node (ref "C10") (pin "1") (pinfunction "1_1") (pintype "passive"))
      (node (ref "C11") (pin "1") (pinfunction "1_1") (pintype "passive"))
      (node (ref "D1") (pin "C") (pinfunction "C_C") (pintype "passive"))
      (node (ref "D2") (pin "C") (pinfunction "C_C") (pintype "passive"))
      (node (ref "FPC50CONN") (pin "A1") (pinfunction "1_A1") (pintype "bidirectional"))
      (node (ref "TP7") (pin "TP") (pinfunction "TP_TP") (pintype "input"))
    )
    (net (code "7") (name "3V3") (class "Default")
      (node (ref "C17") (pin "2") (pinfunction "2_2") (pintype "passive"))
      (node (ref "C18") (pin "2") (pinfunction "2_2") (pintype "passive"))
      (node (ref "C19") (pin "2") (pinfunction "2_2") (pintype "passive"))
      (node (ref "C20") (pin "2") (pinfunction "2_2") (pintype "passive"))
      (node (ref "C21") (pin "2") (pinfunction "2_2") (pintype "passive"))
      (node (ref "C25") (pin "2") (pinfunction "2_2") (pintype "passive"))
      (node (ref "C28") (pin "2") (pinfunction "2_2") (pintype "passive"))
      (node (ref "C29") (pin "2") (pinfunction "2_2") (pintype "passive"))
      (node (ref "C30") (pin "2") (pinfunction "2_2") (pintype "passive"))
      (node (ref "C31") (pin "2") (pinfunction "2_2") (pintype "passive"))
      (node (ref "C5") (pin "1") (pinfunction "1_1") (pintype "passive"))
      (node (ref "FPC50CONN") (pin "A4") (pinfunction "4_A4") (pintype "bidirectional"))
      (node (ref "FPC50CONN") (pin "A43") (pinfunction "43_A43") (pintype "bidirectional"))
      (node (ref "FPC50CONN") (pin "A44") (pinfunction "44_A44") (pintype "bidirectional"))
      (node (ref "IC1") (pin "12") (pinfunction "VDDANA_12") (pintype "bidirectional"))
      (node (ref "IC1") (pin "25") (pinfunction "VDDIOB_1_25") (pintype "bidirectional"))
      (node (ref "IC1") (pin "30") (pinfunction "VDDIOB_2_30") (pintype "bidirectional"))
      (node (ref "IC1") (pin "39") (pinfunction "VDDIO_1_39") (pintype "bidirectional"))
      (node (ref "IC1") (pin "51") (pinfunction "VDDIO_2_51") (pintype "bidirectional"))
      (node (ref "IC1") (pin "63") (pinfunction "VDDIO_3_63") (pintype "bidirectional"))
      (node (ref "IC1") (pin "77") (pinfunction "VDDIO_4_77") (pintype "bidirectional"))
      (node (ref "IC1") (pin "92") (pinfunction "VDDIO_5_92") (pintype "bidirectional"))
      (node (ref "R15") (pin "1") (pinfunction "1_1") (pintype "passive"))
      (node (ref "TAG-CONNECT") (pin "P$1") (pinfunction "PIN1_P$1") (pintype "bidirectional"))
      (node (ref "TP6") (pin "TP") (pinfunction "TP_TP") (pintype "input"))
      (node (ref "U6") (pin "16") (pinfunction "VCC_16") (pintype "bidirectional"))
      (node (ref "VREG") (pin "2") (pinfunction "VOUT_2") (pintype "output"))
      (node (ref "X2") (pin "1") (pinfunction "S_1") (pintype "passive"))
    )
    (net (code "8") (name "5.0V") (class "Default")
      (node (ref "C3") (pin "1") (pinfunction "1_1") (pintype "passive"))
      (node (ref "C6") (pin "1") (pinfunction "1_1") (pintype "passive"))
      (node (ref "C8") (pin "1") (pinfunction "1_1") (pintype "passive"))
      (node (ref "L2") (pin "P$1") (pinfunction "1_P$1") (pintype "passive"))
      (node (ref "R1") (pin "2") (pinfunction "2_2") (pintype "passive"))
      (node (ref "R4") (pin "2") (pinfunction "2_2") (pintype "passive"))
      (node (ref "TP5") (pin "TP") (pinfunction "TP_TP") (pintype "input"))
      (node (ref "U$30") (pin "P2") (pinfunction "P2_P2") (pintype "bidirectional"))
      (node (ref "U$30") (pin "P4") (pinfunction "P4_P4") (pintype "bidirectional"))
      (node (ref "U2") (pin "1") (pinfunction "VOUT_1") (pintype "power_in"))
      (node (ref "U2") (pin "15") (pinfunction "VOUT_15") (pintype "power_in"))
      (node (ref "U2") (pin "16") (pinfunction "VOUT_16") (pintype "power_in"))
      (node (ref "U4") (pin "5") (pinfunction "VIN_5") (pintype "bidirectional"))
      (node (ref "VREG") (pin "3") (pinfunction "VIN_3") (pintype "input"))
    )
    (net (code "9") (name "CTS") (class "Default")
      (node (ref "DE9FEMALE") (pin "P8") (pinfunction "P8_P8") (pintype "bidirectional"))
      (node (ref "U6") (pin "8") (pinfunction "R2IN_8") (pintype "input"))
    )
    (net (code "10") (name "DE") (class "Default")
      (node (ref "FPC50CONN") (pin "A12") (pinfunction "12_A12") (pintype "bidirectional"))
    )
    (net (code "11") (name "DOTCLK") (class "Default")
      (node (ref "FPC50CONN") (pin "A11") (pinfunction "11_A11") (pintype "bidirectional"))
    )
    (net (code "12") (name "ENABLE") (class "Default")
      (node (ref "R13") (pin "2") (pinfunction "2_2") (pintype "passive"))
      (node (ref "U$5") (pin "P$2") (pinfunction "P$2_P$2") (pintype "bidirectional"))
      (node (ref "U2") (pin "11") (pinfunction "EN_11") (pintype "input"))
    )
    (net (code "13") (name "GND") (class "Default")
      (node (ref "B1") (pin "1") (pinfunction "-_1") (pintype "passive"))
      (node (ref "C1") (pin "2") (pinfunction "2_2") (pintype "passive"))
      (node (ref "C10") (pin "2") (pinfunction "2_2") (pintype "passive"))
      (node (ref "C11") (pin "2") (pinfunction "2_2") (pintype "passive"))
      (node (ref "C13") (pin "2") (pinfunction "2_2") (pintype "passive"))
      (node (ref "C14") (pin "2") (pinfunction "2_2") (pintype "passive"))
      (node (ref "C15") (pin "2") (pinfunction "2_2") (pintype "passive"))
      (node (ref "C16") (pin "1") (pinfunction "1_1") (pintype "passive"))
      (node (ref "C17") (pin "1") (pinfunction "1_1") (pintype "passive"))
      (node (ref "C18") (pin "1") (pinfunction "1_1") (pintype "passive"))
      (node (ref "C19") (pin "1") (pinfunction "1_1") (pintype "passive"))
      (node (ref "C2") (pin "2") (pinfunction "2_2") (pintype "passive"))
      (node (ref "C20") (pin "1") (pinfunction "1_1") (pintype "passive"))
      (node (ref "C21") (pin "1") (pinfunction "1_1") (pintype "passive"))
      (node (ref "C24") (pin "2") (pinfunction "2_2") (pintype "passive"))
      (node (ref "C25") (pin "1") (pinfunction "1_1") (pintype "passive"))
      (node (ref "C26") (pin "1") (pinfunction "1_1") (pintype "passive"))
      (node (ref "C27") (pin "1") (pinfunction "1_1") (pintype "passive"))
      (node (ref "C28") (pin "1") (pinfunction "1_1") (pintype "passive"))
      (node (ref "C29") (pin "1") (pinfunction "1_1") (pintype "passive"))
      (node (ref "C3") (pin "2") (pinfunction "2_2") (pintype "passive"))
      (node (ref "C30") (pin "1") (pinfunction "1_1") (pintype "passive"))
      (node (ref "C31") (pin "1") (pinfunction "1_1") (pintype "passive"))
      (node (ref "C4") (pin "2") (pinfunction "2_2") (pintype "passive"))
      (node (ref "C5") (pin "2") (pinfunction "2_2") (pintype "passive"))
      (node (ref "C6") (pin "2") (pinfunction "2_2") (pintype "passive"))
      (node (ref "C7") (pin "2") (pinfunction "2_2") (pintype "passive"))
      (node (ref "C8") (pin "2") (pinfunction "2_2") (pintype "passive"))
      (node (ref "C9") (pin "2") (pinfunction "2_2") (pintype "passive"))
      (node (ref "DE9FEMALE") (pin "G1") (pinfunction "SHIELD_G1") (pintype "bidirectional"))
      (node (ref "DE9FEMALE") (pin "G10") (pinfunction "SHIELD_G10") (pintype "bidirectional"))
      (node (ref "DE9FEMALE") (pin "G11") (pinfunction "SHIELD_G11") (pintype "bidirectional"))
      (node (ref "DE9FEMALE") (pin "G12") (pinfunction "SHIELD_G12") (pintype "bidirectional"))
      (node (ref "DE9FEMALE") (pin "G2") (pinfunction "SHIELD_G2") (pintype "bidirectional"))
      (node (ref "DE9FEMALE") (pin "G3") (pinfunction "SHIELD_G3") (pintype "bidirectional"))
      (node (ref "DE9FEMALE") (pin "G4") (pinfunction "SHIELD_G4") (pintype "bidirectional"))
      (node (ref "DE9FEMALE") (pin "G5") (pinfunction "SHIELD_G5") (pintype "bidirectional"))
      (node (ref "DE9FEMALE") (pin "G6") (pinfunction "SHIELD_G6") (pintype "bidirectional"))
      (node (ref "DE9FEMALE") (pin "G7") (pinfunction "SHIELD_G7") (pintype "bidirectional"))
      (node (ref "DE9FEMALE") (pin "G8") (pinfunction "SHIELD_G8") (pintype "bidirectional"))
      (node (ref "DE9FEMALE") (pin "G9") (pinfunction "SHIELD_G9") (pintype "bidirectional"))
      (node (ref "DE9FEMALE") (pin "P1") (pinfunction "P1_P1") (pintype "bidirectional"))
      (node (ref "FPC50CONN") (pin "A10") (pinfunction "10_A10") (pintype "bidirectional"))
      (node (ref "FPC50CONN") (pin "A13") (pinfunction "13_A13") (pintype "bidirectional"))
      (node (ref "FPC50CONN") (pin "A14") (pinfunction "14_A14") (pintype "bidirectional"))
      (node (ref "FPC50CONN") (pin "A15") (pinfunction "15_A15") (pintype "bidirectional"))
      (node (ref "FPC50CONN") (pin "A16") (pinfunction "16_A16") (pintype "bidirectional"))
      (node (ref "FPC50CONN") (pin "A17") (pinfunction "17_A17") (pintype "bidirectional"))
      (node (ref "FPC50CONN") (pin "A18") (pinfunction "18_A18") (pintype "bidirectional"))
      (node (ref "FPC50CONN") (pin "A19") (pinfunction "19_A19") (pintype "bidirectional"))
      (node (ref "FPC50CONN") (pin "A20") (pinfunction "20_A20") (pintype "bidirectional"))
      (node (ref "FPC50CONN") (pin "A38") (pinfunction "38_A38") (pintype "bidirectional"))
      (node (ref "FPC50CONN") (pin "A45") (pinfunction "45_A45") (pintype "bidirectional"))
      (node (ref "FPC50CONN") (pin "A5") (pinfunction "5_A5") (pintype "bidirectional"))
      (node (ref "FPC50CONN") (pin "A50") (pinfunction "50_A50") (pintype "bidirectional"))
      (node (ref "FPC50CONN") (pin "A6") (pinfunction "6_A6") (pintype "bidirectional"))
      (node (ref "FPC50CONN") (pin "A7") (pinfunction "7_A7") (pintype "bidirectional"))
      (node (ref "FPC50CONN") (pin "A9") (pinfunction "9_A9") (pintype "bidirectional"))
      (node (ref "IC1") (pin "11") (pinfunction "GNDANA_11") (pintype "bidirectional"))
      (node (ref "IC1") (pin "24") (pinfunction "GND_1_24") (pintype "bidirectional"))
      (node (ref "IC1") (pin "31") (pinfunction "GND_2_31") (pintype "bidirectional"))
      (node (ref "IC1") (pin "38") (pinfunction "GND_3_38") (pintype "bidirectional"))
      (node (ref "IC1") (pin "50") (pinfunction "GND_4_50") (pintype "bidirectional"))
      (node (ref "IC1") (pin "62") (pinfunction "GND_5_62") (pintype "bidirectional"))
      (node (ref "IC1") (pin "76") (pinfunction "GND_6_76") (pintype "bidirectional"))
      (node (ref "IC1") (pin "90") (pinfunction "GND_7_90") (pintype "bidirectional"))
      (node (ref "LED1") (pin "C") (pinfunction "C_C") (pintype "passive"))
      (node (ref "R10") (pin "2") (pinfunction "2_2") (pintype "passive"))
      (node (ref "R12") (pin "1") (pinfunction "1_1") (pintype "passive"))
      (node (ref "R16") (pin "1") (pinfunction "1_1") (pintype "passive"))
      (node (ref "R17") (pin "1") (pinfunction "1_1") (pintype "passive"))
      (node (ref "R2") (pin "2") (pinfunction "2_2") (pintype "passive"))
      (node (ref "R3") (pin "2") (pinfunction "2_2") (pintype "passive"))
      (node (ref "R5") (pin "1") (pinfunction "1_1") (pintype "passive"))
      (node (ref "R6") (pin "1") (pinfunction "1_1") (pintype "passive"))
      (node (ref "R7") (pin "1") (pinfunction "1_1") (pintype "passive"))
      (node (ref "SW1") (pin "2") (pinfunction "S_2") (pintype "passive"))
      (node (ref "SW1") (pin "4") (pinfunction "S1_4") (pintype "passive"))
      (node (ref "TAG-CONNECT") (pin "P$5") (pinfunction "PIN5_P$5") (pintype "bidirectional"))
      (node (ref "TP4") (pin "TP") (pinfunction "TP_TP") (pintype "input"))
      (node (ref "TP9") (pin "TP") (pinfunction "TP_TP") (pintype "input"))
      (node (ref "U$30") (pin "P14") (pinfunction "P14_P14") (pintype "bidirectional"))
      (node (ref "U$30") (pin "P25") (pinfunction "P25_P25") (pintype "bidirectional"))
      (node (ref "U$30") (pin "P30") (pinfunction "P30_P30") (pintype "bidirectional"))
      (node (ref "U$30") (pin "P34") (pinfunction "P34_P34") (pintype "bidirectional"))
      (node (ref "U$30") (pin "P39") (pinfunction "P39_P39") (pintype "bidirectional"))
      (node (ref "U$30") (pin "P6") (pinfunction "P6_P6") (pintype "bidirectional"))
      (node (ref "U$30") (pin "P9") (pinfunction "P9_P9") (pintype "bidirectional"))
      (node (ref "U$5") (pin "P$1") (pinfunction "P$1_P$1") (pintype "bidirectional"))
      (node (ref "U2") (pin "10") (pinfunction "SYNC_10") (pintype "input"))
      (node (ref "U2") (pin "13") (pinfunction "GND_13") (pintype "power_in"))
      (node (ref "U2") (pin "5") (pinfunction "PGND_5") (pintype "power_in"))
      (node (ref "U2") (pin "6") (pinfunction "PGND_6") (pintype "power_in"))
      (node (ref "U2") (pin "7") (pinfunction "PGND_7") (pintype "power_in"))
      (node (ref "U2") (pin "P$18") (pinfunction "PGND_P$18") (pintype "power_in"))
      (node (ref "U2") (pin "P$19") (pinfunction "PGND_P$19") (pintype "power_in"))
      (node (ref "U2") (pin "P$20") (pinfunction "PGND_P$20") (pintype "power_in"))
      (node (ref "U2") (pin "P$21") (pinfunction "PGND_P$21") (pintype "power_in"))
      (node (ref "U2") (pin "P$22") (pinfunction "PGND_P$22") (pintype "power_in"))
      (node (ref "U2") (pin "THERMAL") (pinfunction "PGND_THERMAL") (pintype "power_in"))
      (node (ref "U3") (pin "P$10") (pinfunction "VSS1_P$10") (pintype "bidirectional"))
      (node (ref "U3") (pin "P$11") (pinfunction "VSS2_P$11") (pintype "bidirectional"))
      (node (ref "U3") (pin "P$21") (pinfunction "THERMAL_P$21") (pintype "bidirectional"))
      (node (ref "U4") (pin "2") (pinfunction "GND_2") (pintype "bidirectional"))
      (node (ref "U5") (pin "IO3") (pinfunction "IO3_IO3") (pintype "bidirectional"))
      (node (ref "U6") (pin "15") (pinfunction "GND_15") (pintype "bidirectional"))
      (node (ref "USB") (pin "A1B12") (pinfunction "GND_A1B12") (pintype "bidirectional"))
      (node (ref "USB") (pin "B1A12") (pinfunction "GND_B1A12") (pintype "bidirectional"))
      (node (ref "VREG") (pin "1") (pinfunction "GND_1") (pintype "power_in"))
      (node (ref "X2") (pin "3") (pinfunction "S_3") (pintype "passive"))
      (node (ref "X2") (pin "5") (pinfunction "S_5") (pintype "passive"))
      (node (ref "X2") (pin "9") (pinfunction "S_9") (pintype "passive"))
    )
    (net (code "14") (name "KEYCOLUM0") (class "Default")
      (node (ref "IC1") (pin "61") (pinfunction "PC21_61") (pintype "bidirectional"))
      (node (ref "K_7") (pin "P$2") (pinfunction "P$2_P$2") (pintype "bidirectional"))
      (node (ref "K_<") (pin "P$2") (pinfunction "P$2_P$2") (pintype "bidirectional"))
      (node (ref "K_ESC") (pin "P$2") (pinfunction "P$2_P$2") (pintype "bidirectional"))
      (node (ref "K_G") (pin "P$2") (pinfunction "P$2_P$2") (pintype "bidirectional"))
      (node (ref "K_J") (pin "P$2") (pinfunction "P$2_P$2") (pintype "bidirectional"))
      (node (ref "K_NOSCL") (pin "P$2") (pinfunction "P$2_P$2") (pintype "bidirectional"))
      (node (ref "K_RIGHTALT") (pin "P$2") (pinfunction "P$2_P$2") (pintype "bidirectional"))
      (node (ref "K_SETUP") (pin "P$2") (pinfunction "P$2_P$2") (pintype "bidirectional"))
      (node (ref "K_TAB") (pin "P$2") (pinfunction "P$2_P$2") (pintype "bidirectional"))
      (node (ref "K_U") (pin "P$2") (pinfunction "P$2_P$2") (pintype "bidirectional"))
    )
    (net (code "15") (name "KEYCOLUM1") (class "Default")
      (node (ref "IC1") (pin "60") (pinfunction "PC20_60") (pintype "bidirectional"))
      (node (ref "K-1") (pin "P$2") (pinfunction "P$2_P$2") (pintype "bidirectional"))
      (node (ref "K_8") (pin "P$2") (pinfunction "P$2_P$2") (pintype "bidirectional"))
      (node (ref "K_CAPS") (pin "P$2") (pinfunction "P$2_P$2") (pintype "bidirectional"))
      (node (ref "K_H") (pin "P$2") (pinfunction "P$2_P$2") (pintype "bidirectional"))
      (node (ref "K_I") (pin "P$2") (pinfunction "P$2_P$2") (pintype "bidirectional"))
      (node (ref "K_K") (pin "P$2") (pinfunction "P$2_P$2") (pintype "bidirectional"))
      (node (ref "K_LSHIFT") (pin "P$2") (pinfunction "P$2_P$2") (pintype "bidirectional"))
      (node (ref "K_Q") (pin "P$2") (pinfunction "P$2_P$2") (pintype "bidirectional"))
      (node (ref "K_RIGHTMETA") (pin "P$2") (pinfunction "P$2_P$2") (pintype "bidirectional"))
    )
    (net (code "16") (name "KEYCOLUM2") (class "Default")
      (node (ref "IC1") (pin "59") (pinfunction "PC19_59") (pintype "bidirectional"))
      (node (ref "K-2") (pin "P$2") (pinfunction "P$2_P$2") (pintype "bidirectional"))
      (node (ref "K_0") (pin "P$2") (pinfunction "P$2_P$2") (pintype "bidirectional"))
      (node (ref "K_9") (pin "P$2") (pinfunction "P$2_P$2") (pintype "bidirectional"))
      (node (ref "K_>") (pin "P$2") (pinfunction "P$2_P$2") (pintype "bidirectional"))
      (node (ref "K_CONTROL") (pin "P$2") (pinfunction "P$2_P$2") (pintype "bidirectional"))
      (node (ref "K_L") (pin "P$2") (pinfunction "P$2_P$2") (pintype "bidirectional"))
      (node (ref "K_LEFTMETA") (pin "P$2") (pinfunction "P$2_P$2") (pintype "bidirectional"))
      (node (ref "K_O") (pin "P$2") (pinfunction "P$2_P$2") (pintype "bidirectional"))
      (node (ref "K_W") (pin "P$2") (pinfunction "P$2_P$2") (pintype "bidirectional"))
      (node (ref "K_Z") (pin "P$2") (pinfunction "P$2_P$2") (pintype "bidirectional"))
    )
    (net (code "17") (name "KEYCOLUM3") (class "Default")
      (node (ref "IC1") (pin "58") (pinfunction "PC18_58") (pintype "bidirectional"))
      (node (ref "K_3") (pin "P$2") (pinfunction "P$2_P$2") (pintype "bidirectional"))
      (node (ref "K_?") (pin "P$2") (pinfunction "P$2_P$2") (pintype "bidirectional"))
      (node (ref "K_A") (pin "P$2") (pinfunction "P$2_P$2") (pintype "bidirectional"))
      (node (ref "K_E") (pin "P$2") (pinfunction "P$2_P$2") (pintype "bidirectional"))
      (node (ref "K_LEFT") (pin "P$2") (pinfunction "P$2_P$2") (pintype "bidirectional"))
      (node (ref "K_LEFTALT") (pin "P$2") (pinfunction "P$2_P$2") (pintype "bidirectional"))
      (node (ref "K_P") (pin "P$2") (pinfunction "P$2_P$2") (pintype "bidirectional"))
      (node (ref "K_SEMI") (pin "P$2") (pinfunction "P$2_P$2") (pintype "bidirectional"))
      (node (ref "K_USCORE") (pin "P$2") (pinfunction "P$2_P$2") (pintype "bidirectional"))
      (node (ref "K_X") (pin "P$2") (pinfunction "P$2_P$2") (pintype "bidirectional"))
    )
    (net (code "18") (name "KEYCOLUM4") (class "Default")
      (node (ref "IC1") (pin "57") (pinfunction "PC17_57") (pintype "bidirectional"))
      (node (ref "K_4") (pin "P$2") (pinfunction "P$2_P$2") (pintype "bidirectional"))
      (node (ref "K_C") (pin "P$2") (pinfunction "P$2_P$2") (pintype "bidirectional"))
      (node (ref "K_DOWN") (pin "P$2") (pinfunction "P$2_P$2") (pintype "bidirectional"))
      (node (ref "K_PLUS") (pin "P$2") (pinfunction "P$2_P$2") (pintype "bidirectional"))
      (node (ref "K_QUOTE") (pin "P$2") (pinfunction "P$2_P$2") (pintype "bidirectional"))
      (node (ref "K_R") (pin "P$2") (pinfunction "P$2_P$2") (pintype "bidirectional"))
      (node (ref "K_RSHIFT") (pin "P$2") (pinfunction "P$2_P$2") (pintype "bidirectional"))
      (node (ref "K_S") (pin "P$2") (pinfunction "P$2_P$2") (pintype "bidirectional"))
      (node (ref "K_SPACE") (pin "P$2") (pinfunction "P$2_P$2") (pintype "bidirectional"))
      (node (ref "K_{") (pin "P$2") (pinfunction "P$2_P$2") (pintype "bidirectional"))
    )
    (net (code "19") (name "KEYCOLUM5") (class "Default")
      (node (ref "IC1") (pin "56") (pinfunction "PC16_56") (pintype "bidirectional"))
      (node (ref "K-5") (pin "P$2") (pinfunction "P$2_P$2") (pintype "bidirectional"))
      (node (ref "K_D") (pin "P$2") (pinfunction "P$2_P$2") (pintype "bidirectional"))
      (node (ref "K_N") (pin "P$2") (pinfunction "P$2_P$2") (pintype "bidirectional"))
      (node (ref "K_PIPE") (pin "P$2") (pinfunction "P$2_P$2") (pintype "bidirectional"))
      (node (ref "K_RETURN") (pin "P$2") (pinfunction "P$2_P$2") (pintype "bidirectional"))
      (node (ref "K_T") (pin "P$2") (pinfunction "P$2_P$2") (pintype "bidirectional"))
      (node (ref "K_TILDE") (pin "P$2") (pinfunction "P$2_P$2") (pintype "bidirectional"))
      (node (ref "K_UP") (pin "P$2") (pinfunction "P$2_P$2") (pintype "bidirectional"))
      (node (ref "K_V") (pin "P$2") (pinfunction "P$2_P$2") (pintype "bidirectional"))
      (node (ref "K_}") (pin "P$2") (pinfunction "P$2_P$2") (pintype "bidirectional"))
    )
    (net (code "20") (name "KEYCOLUM6") (class "Default")
      (node (ref "IC1") (pin "45") (pinfunction "PC15_45") (pintype "bidirectional"))
      (node (ref "K_6") (pin "P$2") (pinfunction "P$2_P$2") (pintype "bidirectional"))
      (node (ref "K_B") (pin "P$2") (pinfunction "P$2_P$2") (pintype "bidirectional"))
      (node (ref "K_BACK") (pin "P$2") (pinfunction "P$2_P$2") (pintype "bidirectional"))
      (node (ref "K_BREAK") (pin "P$2") (pinfunction "P$2_P$2") (pintype "bidirectional"))
      (node (ref "K_DEL") (pin "P$2") (pinfunction "P$2_P$2") (pintype "bidirectional"))
      (node (ref "K_F") (pin "P$2") (pinfunction "P$2_P$2") (pintype "bidirectional"))
      (node (ref "K_LINE") (pin "P$2") (pinfunction "P$2_P$2") (pintype "bidirectional"))
      (node (ref "K_M") (pin "P$2") (pinfunction "P$2_P$2") (pintype "bidirectional"))
      (node (ref "K_RIGHT") (pin "P$2") (pinfunction "P$2_P$2") (pintype "bidirectional"))
      (node (ref "K_Y") (pin "P$2") (pinfunction "P$2_P$2") (pintype "bidirectional"))
    )
    (net (code "21") (name "KEYROW0") (class "Default")
      (node (ref "IC1") (pin "44") (pinfunction "PC14_44") (pintype "bidirectional"))
      (node (ref "K-1") (pin "P$1") (pinfunction "P$1_P$1") (pintype "bidirectional"))
      (node (ref "K-2") (pin "P$1") (pinfunction "P$1_P$1") (pintype "bidirectional"))
      (node (ref "K-5") (pin "P$1") (pinfunction "P$1_P$1") (pintype "bidirectional"))
      (node (ref "K_3") (pin "P$1") (pinfunction "P$1_P$1") (pintype "bidirectional"))
      (node (ref "K_4") (pin "P$1") (pinfunction "P$1_P$1") (pintype "bidirectional"))
      (node (ref "K_6") (pin "P$1") (pinfunction "P$1_P$1") (pintype "bidirectional"))
      (node (ref "K_ESC") (pin "P$1") (pinfunction "P$1_P$1") (pintype "bidirectional"))
    )
    (net (code "22") (name "KEYROW1") (class "Default")
      (node (ref "IC1") (pin "43") (pinfunction "PC13_43") (pintype "bidirectional"))
      (node (ref "K_E") (pin "P$1") (pinfunction "P$1_P$1") (pintype "bidirectional"))
      (node (ref "K_Q") (pin "P$1") (pinfunction "P$1_P$1") (pintype "bidirectional"))
      (node (ref "K_R") (pin "P$1") (pinfunction "P$1_P$1") (pintype "bidirectional"))
      (node (ref "K_SETUP") (pin "P$1") (pinfunction "P$1_P$1") (pintype "bidirectional"))
      (node (ref "K_T") (pin "P$1") (pinfunction "P$1_P$1") (pintype "bidirectional"))
      (node (ref "K_W") (pin "P$1") (pinfunction "P$1_P$1") (pintype "bidirectional"))
      (node (ref "K_Y") (pin "P$1") (pinfunction "P$1_P$1") (pintype "bidirectional"))
    )
    (net (code "23") (name "KEYROW2") (class "Default")
      (node (ref "IC1") (pin "42") (pinfunction "PC12_42") (pintype "bidirectional"))
      (node (ref "K_A") (pin "P$1") (pinfunction "P$1_P$1") (pintype "bidirectional"))
      (node (ref "K_CAPS") (pin "P$1") (pinfunction "P$1_P$1") (pintype "bidirectional"))
      (node (ref "K_CONTROL") (pin "P$1") (pinfunction "P$1_P$1") (pintype "bidirectional"))
      (node (ref "K_D") (pin "P$1") (pinfunction "P$1_P$1") (pintype "bidirectional"))
      (node (ref "K_F") (pin "P$1") (pinfunction "P$1_P$1") (pintype "bidirectional"))
      (node (ref "K_S") (pin "P$1") (pinfunction "P$1_P$1") (pintype "bidirectional"))
      (node (ref "K_TAB") (pin "P$1") (pinfunction "P$1_P$1") (pintype "bidirectional"))
    )
    (net (code "24") (name "KEYROW3") (class "Default")
      (node (ref "IC1") (pin "41") (pinfunction "PC11_41") (pintype "bidirectional"))
      (node (ref "K_B") (pin "P$1") (pinfunction "P$1_P$1") (pintype "bidirectional"))
      (node (ref "K_C") (pin "P$1") (pinfunction "P$1_P$1") (pintype "bidirectional"))
      (node (ref "K_LSHIFT") (pin "P$1") (pinfunction "P$1_P$1") (pintype "bidirectional"))
      (node (ref "K_NOSCL") (pin "P$1") (pinfunction "P$1_P$1") (pintype "bidirectional"))
      (node (ref "K_V") (pin "P$1") (pinfunction "P$1_P$1") (pintype "bidirectional"))
      (node (ref "K_X") (pin "P$1") (pinfunction "P$1_P$1") (pintype "bidirectional"))
      (node (ref "K_Z") (pin "P$1") (pinfunction "P$1_P$1") (pintype "bidirectional"))
    )
    (net (code "25") (name "KEYROW4") (class "Default")
      (node (ref "IC1") (pin "40") (pinfunction "PC10_40") (pintype "bidirectional"))
      (node (ref "K_LEFTALT") (pin "P$1") (pinfunction "P$1_P$1") (pintype "bidirectional"))
      (node (ref "K_LEFTMETA") (pin "P$1") (pinfunction "P$1_P$1") (pintype "bidirectional"))
      (node (ref "K_M") (pin "P$1") (pinfunction "P$1_P$1") (pintype "bidirectional"))
      (node (ref "K_N") (pin "P$1") (pinfunction "P$1_P$1") (pintype "bidirectional"))
      (node (ref "K_RIGHTALT") (pin "P$1") (pinfunction "P$1_P$1") (pintype "bidirectional"))
      (node (ref "K_RIGHTMETA") (pin "P$1") (pinfunction "P$1_P$1") (pintype "bidirectional"))
      (node (ref "K_SPACE") (pin "P$1") (pinfunction "P$1_P$1") (pintype "bidirectional"))
    )
    (net (code "26") (name "KEYROW5") (class "Default")
      (node (ref "IC1") (pin "23") (pinfunction "PC07_23") (pintype "bidirectional"))
      (node (ref "K_7") (pin "P$1") (pinfunction "P$1_P$1") (pintype "bidirectional"))
      (node (ref "K_8") (pin "P$1") (pinfunction "P$1_P$1") (pintype "bidirectional"))
      (node (ref "K_9") (pin "P$1") (pinfunction "P$1_P$1") (pintype "bidirectional"))
      (node (ref "K_DOWN") (pin "P$1") (pinfunction "P$1_P$1") (pintype "bidirectional"))
      (node (ref "K_LEFT") (pin "P$1") (pinfunction "P$1_P$1") (pintype "bidirectional"))
      (node (ref "K_RIGHT") (pin "P$1") (pinfunction "P$1_P$1") (pintype "bidirectional"))
      (node (ref "K_UP") (pin "P$1") (pinfunction "P$1_P$1") (pintype "bidirectional"))
    )
    (net (code "27") (name "KEYROW6") (class "Default")
      (node (ref "IC1") (pin "22") (pinfunction "PC06_22") (pintype "bidirectional"))
      (node (ref "K_0") (pin "P$1") (pinfunction "P$1_P$1") (pintype "bidirectional"))
      (node (ref "K_BACK") (pin "P$1") (pinfunction "P$1_P$1") (pintype "bidirectional"))
      (node (ref "K_I") (pin "P$1") (pinfunction "P$1_P$1") (pintype "bidirectional"))
      (node (ref "K_PLUS") (pin "P$1") (pinfunction "P$1_P$1") (pintype "bidirectional"))
      (node (ref "K_TILDE") (pin "P$1") (pinfunction "P$1_P$1") (pintype "bidirectional"))
      (node (ref "K_U") (pin "P$1") (pinfunction "P$1_P$1") (pintype "bidirectional"))
      (node (ref "K_USCORE") (pin "P$1") (pinfunction "P$1_P$1") (pintype "bidirectional"))
    )
    (net (code "28") (name "KEYROW7") (class "Default")
      (node (ref "IC1") (pin "21") (pinfunction "PC05_21") (pintype "bidirectional"))
      (node (ref "K_BREAK") (pin "P$1") (pinfunction "P$1_P$1") (pintype "bidirectional"))
      (node (ref "K_G") (pin "P$1") (pinfunction "P$1_P$1") (pintype "bidirectional"))
      (node (ref "K_H") (pin "P$1") (pinfunction "P$1_P$1") (pintype "bidirectional"))
      (node (ref "K_O") (pin "P$1") (pinfunction "P$1_P$1") (pintype "bidirectional"))
      (node (ref "K_P") (pin "P$1") (pinfunction "P$1_P$1") (pintype "bidirectional"))
      (node (ref "K_{") (pin "P$1") (pinfunction "P$1_P$1") (pintype "bidirectional"))
      (node (ref "K_}") (pin "P$1") (pinfunction "P$1_P$1") (pintype "bidirectional"))
    )
    (net (code "29") (name "KEYROW8") (class "Default")
      (node (ref "IC1") (pin "6") (pinfunction "PC03_6") (pintype "bidirectional"))
      (node (ref "K_DEL") (pin "P$1") (pinfunction "P$1_P$1") (pintype "bidirectional"))
      (node (ref "K_J") (pin "P$1") (pinfunction "P$1_P$1") (pintype "bidirectional"))
      (node (ref "K_K") (pin "P$1") (pinfunction "P$1_P$1") (pintype "bidirectional"))
      (node (ref "K_L") (pin "P$1") (pinfunction "P$1_P$1") (pintype "bidirectional"))
      (node (ref "K_QUOTE") (pin "P$1") (pinfunction "P$1_P$1") (pintype "bidirectional"))
      (node (ref "K_RETURN") (pin "P$1") (pinfunction "P$1_P$1") (pintype "bidirectional"))
      (node (ref "K_SEMI") (pin "P$1") (pinfunction "P$1_P$1") (pintype "bidirectional"))
    )
    (net (code "30") (name "KEYROW9") (class "Default")
      (node (ref "IC1") (pin "5") (pinfunction "PC02_5") (pintype "bidirectional"))
      (node (ref "K_<") (pin "P$1") (pinfunction "P$1_P$1") (pintype "bidirectional"))
      (node (ref "K_>") (pin "P$1") (pinfunction "P$1_P$1") (pintype "bidirectional"))
      (node (ref "K_?") (pin "P$1") (pinfunction "P$1_P$1") (pintype "bidirectional"))
      (node (ref "K_LINE") (pin "P$1") (pinfunction "P$1_P$1") (pintype "bidirectional"))
      (node (ref "K_PIPE") (pin "P$1") (pinfunction "P$1_P$1") (pintype "bidirectional"))
      (node (ref "K_RSHIFT") (pin "P$1") (pinfunction "P$1_P$1") (pintype "bidirectional"))
    )
    (net (code "31") (name "LBO") (class "Default")
      (node (ref "T1") (pin "B") (pinfunction "B_B") (pintype "passive"))
      (node (ref "U2") (pin "12") (pinfunction "LBO_12") (pintype "output"))
    )
    (net (code "32") (name "LCD0") (class "Default")
      (node (ref "FPC50CONN") (pin "A36") (pinfunction "36_A36") (pintype "bidirectional"))
      (node (ref "IC1") (pin "97") (pinfunction "PB00_97") (pintype "bidirectional"))
    )
    (net (code "33") (name "LCD1") (class "Default")
      (node (ref "FPC50CONN") (pin "A35") (pinfunction "35_A35") (pintype "bidirectional"))
      (node (ref "IC1") (pin "98") (pinfunction "PB01_98") (pintype "bidirectional"))
    )
    (net (code "34") (name "LCD2") (class "Default")
      (node (ref "FPC50CONN") (pin "A34") (pinfunction "34_A34") (pintype "bidirectional"))
      (node (ref "IC1") (pin "99") (pinfunction "PB02_99") (pintype "bidirectional"))
    )
    (net (code "35") (name "LCD3") (class "Default")
      (node (ref "FPC50CONN") (pin "A33") (pinfunction "33_A33") (pintype "bidirectional"))
      (node (ref "IC1") (pin "100") (pinfunction "PB03_100") (pintype "bidirectional"))
    )
    (net (code "36") (name "LCD4") (class "Default")
      (node (ref "FPC50CONN") (pin "A32") (pinfunction "32_A32") (pintype "bidirectional"))
      (node (ref "IC1") (pin "9") (pinfunction "PB04_9") (pintype "bidirectional"))
    )
    (net (code "37") (name "LCD5") (class "Default")
      (node (ref "FPC50CONN") (pin "A31") (pinfunction "31_A31") (pintype "bidirectional"))
      (node (ref "IC1") (pin "10") (pinfunction "PB05_10") (pintype "bidirectional"))
    )
    (net (code "38") (name "LCD6") (class "Default")
      (node (ref "FPC50CONN") (pin "A30") (pinfunction "30_A30") (pintype "bidirectional"))
      (node (ref "IC1") (pin "13") (pinfunction "PB06_13") (pintype "bidirectional"))
    )
    (net (code "39") (name "LCD7") (class "Default")
      (node (ref "FPC50CONN") (pin "A29") (pinfunction "29_A29") (pintype "bidirectional"))
      (node (ref "IC1") (pin "14") (pinfunction "PB07_14") (pintype "bidirectional"))
    )
    (net (code "40") (name "LCD8") (class "Default")
      (node (ref "FPC50CONN") (pin "A28") (pinfunction "28_A28") (pintype "bidirectional"))
      (node (ref "IC1") (pin "15") (pinfunction "PB08_15") (pintype "bidirectional"))
    )
    (net (code "41") (name "LCD9") (class "Default")
      (node (ref "FPC50CONN") (pin "A27") (pinfunction "27_A27") (pintype "bidirectional"))
      (node (ref "IC1") (pin "16") (pinfunction "PB09_16") (pintype "bidirectional"))
    )
    (net (code "42") (name "LCD10") (class "Default")
      (node (ref "FPC50CONN") (pin "A26") (pinfunction "26_A26") (pintype "bidirectional"))
      (node (ref "IC1") (pin "32") (pinfunction "PB10_32") (pintype "bidirectional"))
    )
    (net (code "43") (name "LCD11") (class "Default")
      (node (ref "FPC50CONN") (pin "A25") (pinfunction "25_A25") (pintype "bidirectional"))
      (node (ref "IC1") (pin "33") (pinfunction "PB11_33") (pintype "bidirectional"))
    )
    (net (code "44") (name "LCD12") (class "Default")
      (node (ref "FPC50CONN") (pin "A24") (pinfunction "24_A24") (pintype "bidirectional"))
      (node (ref "IC1") (pin "34") (pinfunction "PB12_34") (pintype "bidirectional"))
    )
    (net (code "45") (name "LCD13") (class "Default")
      (node (ref "FPC50CONN") (pin "A23") (pinfunction "23_A23") (pintype "bidirectional"))
      (node (ref "IC1") (pin "35") (pinfunction "PB13_35") (pintype "bidirectional"))
    )
    (net (code "46") (name "LCD14") (class "Default")
      (node (ref "FPC50CONN") (pin "A22") (pinfunction "22_A22") (pintype "bidirectional"))
      (node (ref "IC1") (pin "36") (pinfunction "PB14_36") (pintype "bidirectional"))
    )
    (net (code "47") (name "LCD15") (class "Default")
      (node (ref "FPC50CONN") (pin "A21") (pinfunction "21_A21") (pintype "bidirectional"))
      (node (ref "IC1") (pin "37") (pinfunction "PB15_37") (pintype "bidirectional"))
    )
    (net (code "48") (name "LCD_CS") (class "Default")
      (node (ref "FPC50CONN") (pin "A42") (pinfunction "42_A42") (pintype "bidirectional"))
      (node (ref "IC1") (pin "78") (pinfunction "PB22_78") (pintype "bidirectional"))
    )
    (net (code "49") (name "LCD_D{slash}C") (class "Default")
      (node (ref "FPC50CONN") (pin "A41") (pinfunction "41_A41") (pintype "bidirectional"))
      (node (ref "IC1") (pin "79") (pinfunction "PB23_79") (pintype "bidirectional"))
    )
    (net (code "50") (name "LCD_RD") (class "Default")
      (node (ref "FPC50CONN") (pin "A39") (pinfunction "39_A39") (pintype "bidirectional"))
      (node (ref "IC1") (pin "64") (pinfunction "PB16_64") (pintype "bidirectional"))
    )
    (net (code "51") (name "LCD_RESET") (class "Default")
      (node (ref "FPC50CONN") (pin "A8") (pinfunction "8_A8") (pintype "bidirectional"))
      (node (ref "IC1") (pin "95") (pinfunction "PB30_95") (pintype "bidirectional"))
    )
    (net (code "52") (name "LCD_W{slash}R") (class "Default")
      (node (ref "FPC50CONN") (pin "A40") (pinfunction "40_A40") (pintype "bidirectional"))
      (node (ref "IC1") (pin "65") (pinfunction "PB17_65") (pintype "bidirectional"))
    )
    (net (code "53") (name "LEDK") (class "Default")
      (node (ref "C9") (pin "1") (pinfunction "1_1") (pintype "passive"))
      (node (ref "D1") (pin "A") (pinfunction "A_A") (pintype "passive"))
      (node (ref "FPC50CONN") (pin "A2") (pinfunction "2_A2") (pintype "bidirectional"))
      (node (ref "FPC50CONN") (pin "A3") (pinfunction "3_A3") (pintype "bidirectional"))
      (node (ref "R12") (pin "2") (pinfunction "2_2") (pintype "passive"))
      (node (ref "TP8") (pin "TP") (pinfunction "TP_TP") (pintype "input"))
      (node (ref "U4") (pin "3") (pinfunction "FB_3") (pintype "bidirectional"))
    )
    (net (code "54") (name "Net-(DE9FEMALE-PadP2)") (class "Default")
      (node (ref "DE9FEMALE") (pin "P2") (pinfunction "P2_P2") (pintype "bidirectional"))
      (node (ref "DE9FEMALE") (pin "P5") (pinfunction "P5_P5") (pintype "bidirectional"))
      (node (ref "DE9FEMALE") (pin "P9") (pinfunction "P9_P9") (pintype "bidirectional"))
    )
    (net (code "55") (name "Net-(IC1-PA00)") (class "Default")
      (node (ref "C27") (pin "2") (pinfunction "2_2") (pintype "passive"))
      (node (ref "IC1") (pin "1") (pinfunction "PA00_1") (pintype "bidirectional"))
      (node (ref "X1") (pin "P$1") (pinfunction "P$1_P$1") (pintype "bidirectional"))
    )
    (net (code "56") (name "Net-(IC1-PA01)") (class "Default")
      (node (ref "C26") (pin "2") (pinfunction "2_2") (pintype "passive"))
      (node (ref "IC1") (pin "2") (pinfunction "PA01_2") (pintype "bidirectional"))
      (node (ref "X1") (pin "P$2") (pinfunction "P$2_P$2") (pintype "bidirectional"))
    )
    (net (code "57") (name "Net-(IC1-PA10)") (class "Default")
      (node (ref "IC1") (pin "28") (pinfunction "PA10_28") (pintype "bidirectional"))
      (node (ref "SJ2") (pin "2") (pinfunction "2_2") (pintype "passive"))
    )
    (net (code "58") (name "Net-(IC1-PA11)") (class "Default")
      (node (ref "IC1") (pin "29") (pinfunction "PA11_29") (pintype "bidirectional"))
      (node (ref "SJ1") (pin "2") (pinfunction "2_2") (pintype "passive"))
    )
    (net (code "59") (name "Net-(IC1-VDDCORE)") (class "Default")
      (node (ref "C14") (pin "1") (pinfunction "1_1") (pintype "passive"))
      (node (ref "C15") (pin "1") (pinfunction "1_1") (pintype "passive"))
      (node (ref "C16") (pin "2") (pinfunction "2_2") (pintype "passive"))
      (node (ref "IC1") (pin "89") (pinfunction "VDDCORE_89") (pintype "bidirectional"))
      (node (ref "L3") (pin "P$1") (pinfunction "1_P$1") (pintype "passive"))
    )
    (net (code "60") (name "Net-(IC1-VSW)") (class "Default")
      (node (ref "IC1") (pin "91") (pinfunction "VSW_91") (pintype "bidirectional"))
      (node (ref "L3") (pin "P$2") (pinfunction "2_P$2") (pintype "passive"))
    )
    (net (code "61") (name "Net-(L1-2)") (class "Default")
      (node (ref "L1") (pin "P$2") (pinfunction "2_P$2") (pintype "passive"))
      (node (ref "U2") (pin "3") (pinfunction "SW_3") (pintype "input"))
      (node (ref "U2") (pin "4") (pinfunction "SW_4") (pintype "input"))
    )
    (net (code "62") (name "Net-(L2-2)") (class "Default")
      (node (ref "D2") (pin "A") (pinfunction "A_A") (pintype "passive"))
      (node (ref "L2") (pin "P$2") (pinfunction "2_P$2") (pintype "passive"))
      (node (ref "U4") (pin "1") (pinfunction "SW_1") (pintype "bidirectional"))
    )
    (net (code "63") (name "Net-(LED1-PadA)") (class "Default")
      (node (ref "LED1") (pin "A") (pinfunction "A_A") (pintype "passive"))
      (node (ref "R20") (pin "1") (pinfunction "1_1") (pintype "passive"))
    )
    (net (code "64") (name "Net-(LED2-PadC)") (class "Default")
      (node (ref "LED2") (pin "C") (pinfunction "C_C") (pintype "passive"))
      (node (ref "R11") (pin "2") (pinfunction "2_2") (pintype "passive"))
    )
    (net (code "65") (name "Net-(LED3-PadC)") (class "Default")
      (node (ref "LED3") (pin "C") (pinfunction "C_C") (pintype "passive"))
      (node (ref "R14") (pin "2") (pinfunction "2_2") (pintype "passive"))
    )
    (net (code "66") (name "Net-(R20-Pad2)") (class "Default")
      (node (ref "R20") (pin "2") (pinfunction "2_2") (pintype "passive"))
      (node (ref "T1") (pin "C") (pinfunction "C_C") (pintype "passive"))
    )
    (net (code "67") (name "Net-(U2-FB)") (class "Default")
      (node (ref "R4") (pin "1") (pinfunction "1_1") (pintype "passive"))
      (node (ref "R6") (pin "2") (pinfunction "2_2") (pintype "passive"))
      (node (ref "U2") (pin "14") (pinfunction "FB_14") (pintype "input"))
    )
    (net (code "68") (name "Net-(U2-LBI)") (class "Default")
      (node (ref "R7") (pin "2") (pinfunction "2_2") (pintype "passive"))
      (node (ref "R8") (pin "1") (pinfunction "1_1") (pintype "passive"))
      (node (ref "U2") (pin "9") (pinfunction "LBI_9") (pintype "input"))
    )
    (net (code "69") (name "Net-(U3-PROG1)") (class "Default")
      (node (ref "R16") (pin "2") (pinfunction "2_2") (pintype "passive"))
      (node (ref "U3") (pin "P$13") (pinfunction "PROG1_P$13") (pintype "bidirectional"))
    )
    (net (code "70") (name "Net-(U3-PROG3)") (class "Default")
      (node (ref "R17") (pin "2") (pinfunction "2_2") (pintype "passive"))
      (node (ref "U3") (pin "P$12") (pinfunction "PROG3_P$12") (pintype "bidirectional"))
    )
    (net (code "71") (name "Net-(U3-STAT1{slash}LBO)") (class "Default")
      (node (ref "R11") (pin "1") (pinfunction "1_1") (pintype "passive"))
      (node (ref "U3") (pin "P$8") (pinfunction "STAT1/LBO_P$8") (pintype "bidirectional"))
    )
    (net (code "72") (name "Net-(U3-STAT2)") (class "Default")
      (node (ref "R14") (pin "1") (pinfunction "1_1") (pintype "passive"))
      (node (ref "U3") (pin "P$7") (pinfunction "STAT2_P$7") (pintype "bidirectional"))
    )
    (net (code "73") (name "Net-(U3-THERM)") (class "Default")
      (node (ref "R5") (pin "2") (pinfunction "2_2") (pintype "passive"))
      (node (ref "U3") (pin "P$5") (pinfunction "THERM_P$5") (pintype "bidirectional"))
    )
    (net (code "74") (name "Net-(U3-VPCC)") (class "Default")
      (node (ref "R10") (pin "1") (pinfunction "1_1") (pintype "passive"))
      (node (ref "R9") (pin "1") (pinfunction "1_1") (pintype "passive"))
      (node (ref "U3") (pin "P$2") (pinfunction "VPCC_P$2") (pintype "bidirectional"))
    )
    (net (code "75") (name "Net-(U6-C1+)") (class "Default")
      (node (ref "C22") (pin "1") (pinfunction "1_1") (pintype "passive"))
      (node (ref "U6") (pin "1") (pinfunction "C1+_1") (pintype "bidirectional"))
    )
    (net (code "76") (name "Net-(U6-C1-)") (class "Default")
      (node (ref "C22") (pin "2") (pinfunction "2_2") (pintype "passive"))
      (node (ref "U6") (pin "3") (pinfunction "C1-_3") (pintype "bidirectional"))
    )
    (net (code "77") (name "Net-(U6-C2+)") (class "Default")
      (node (ref "C23") (pin "1") (pinfunction "1_1") (pintype "passive"))
      (node (ref "U6") (pin "4") (pinfunction "C2+_4") (pintype "bidirectional"))
    )
    (net (code "78") (name "Net-(U6-C2-)") (class "Default")
      (node (ref "C23") (pin "2") (pinfunction "2_2") (pintype "passive"))
      (node (ref "U6") (pin "5") (pinfunction "C2-_5") (pintype "bidirectional"))
    )
    (net (code "79") (name "Net-(U6-V+)") (class "Default")
      (node (ref "C24") (pin "1") (pinfunction "1_1") (pintype "passive"))
      (node (ref "U6") (pin "2") (pinfunction "V+_2") (pintype "bidirectional"))
    )
    (net (code "80") (name "Net-(U6-V-)") (class "Default")
      (node (ref "C13") (pin "1") (pinfunction "1_1") (pintype "passive"))
      (node (ref "U6") (pin "6") (pinfunction "V-_6") (pintype "bidirectional"))
    )
    (net (code "81") (name "Net-(USB-CC1)") (class "Default")
      (node (ref "R2") (pin "1") (pinfunction "1_1") (pintype "passive"))
      (node (ref "USB") (pin "A5") (pinfunction "CC1_A5") (pintype "bidirectional"))
    )
    (net (code "82") (name "Net-(USB-CC2)") (class "Default")
      (node (ref "R3") (pin "1") (pinfunction "1_1") (pintype "passive"))
      (node (ref "USB") (pin "B5") (pinfunction "CC2_B5") (pintype "bidirectional"))
    )
    (net (code "83") (name "PB31") (class "Default")
      (node (ref "IC1") (pin "96") (pinfunction "PB31_96") (pintype "bidirectional"))
      (node (ref "U$30") (pin "P1") (pinfunction "P1_P1") (pintype "bidirectional"))
    )
    (net (code "84") (name "PI_RX") (class "Default")
      (node (ref "IC1") (pin "47") (pinfunction "PA13_47") (pintype "bidirectional"))
      (node (ref "U$30") (pin "P8") (pinfunction "P8_P8") (pintype "bidirectional"))
    )
    (net (code "85") (name "PI_TX") (class "Default")
      (node (ref "IC1") (pin "46") (pinfunction "PA12_46") (pintype "bidirectional"))
      (node (ref "U$30") (pin "P10") (pinfunction "P10_P10") (pintype "bidirectional"))
    )
    (net (code "86") (name "PWM") (class "Default")
      (node (ref "R1") (pin "1") (pinfunction "1_1") (pintype "passive"))
      (node (ref "TP17") (pin "TP") (pinfunction "TP_TP") (pintype "input"))
      (node (ref "U4") (pin "4") (pinfunction "SHDN_4") (pintype "bidirectional"))
    )
    (net (code "87") (name "RESET") (class "Default")
      (node (ref "IC1") (pin "88") (pinfunction "RESETN_88") (pintype "bidirectional"))
      (node (ref "R15") (pin "2") (pinfunction "2_2") (pintype "passive"))
      (node (ref "SW1") (pin "1") (pinfunction "P_1") (pintype "passive"))
      (node (ref "SW1") (pin "3") (pinfunction "P1_3") (pintype "passive"))
      (node (ref "TAG-CONNECT") (pin "P$10") (pinfunction "PIN10_P$10") (pintype "bidirectional"))
      (node (ref "TP14") (pin "TP") (pinfunction "TP_TP") (pintype "input"))
      (node (ref "X2") (pin "10") (pinfunction "S_10") (pintype "passive"))
    )
    (net (code "88") (name "RTS") (class "Default")
      (node (ref "DE9FEMALE") (pin "P7") (pinfunction "P7_P7") (pintype "bidirectional"))
      (node (ref "U6") (pin "7") (pinfunction "T2OUT_7") (pintype "output"))
    )
    (net (code "89") (name "RXD") (class "Default")
      (node (ref "DE9FEMALE") (pin "P3") (pinfunction "P3_P3") (pintype "bidirectional"))
      (node (ref "U6") (pin "13") (pinfunction "R1IN_13") (pintype "input"))
    )
    (net (code "90") (name "SDO") (class "Default")
      (node (ref "FPC50CONN") (pin "A37") (pinfunction "37_A37") (pintype "bidirectional"))
    )
    (net (code "91") (name "SWCLK") (class "Default")
      (node (ref "IC1") (pin "93") (pinfunction "PA30_93") (pintype "bidirectional"))
      (node (ref "TAG-CONNECT") (pin "P$4") (pinfunction "PIN4_P$4") (pintype "bidirectional"))
      (node (ref "TP15") (pin "TP") (pinfunction "TP_TP") (pintype "input"))
      (node (ref "X2") (pin "4") (pinfunction "S_4") (pintype "passive"))
    )
    (net (code "92") (name "SWDIO") (class "Default")
      (node (ref "IC1") (pin "94") (pinfunction "PA31_94") (pintype "bidirectional"))
      (node (ref "TAG-CONNECT") (pin "P$2") (pinfunction "PIN2_P$2") (pintype "bidirectional"))
      (node (ref "TP16") (pin "TP") (pinfunction "TP_TP") (pintype "input"))
      (node (ref "X2") (pin "2") (pinfunction "S_2") (pintype "passive"))
    )
    (net (code "93") (name "TXD") (class "Default")
      (node (ref "DE9FEMALE") (pin "P4") (pinfunction "P4_P4") (pintype "bidirectional"))
      (node (ref "U6") (pin "14") (pinfunction "T1OUT_14") (pintype "output"))
    )
    (net (code "94") (name "UART_CTS") (class "Default")
      (node (ref "SJ1") (pin "1") (pinfunction "1_1") (pintype "passive"))
      (node (ref "U6") (pin "10") (pinfunction "T2IN_10") (pintype "input"))
    )
    (net (code "95") (name "UART_RTS") (class "Default")
      (node (ref "SJ2") (pin "1") (pinfunction "1_1") (pintype "passive"))
      (node (ref "U6") (pin "9") (pinfunction "R2OUT_9") (pintype "output"))
    )
    (net (code "96") (name "UART_RX") (class "Default")
      (node (ref "IC1") (pin "27") (pinfunction "PA09_27") (pintype "bidirectional"))
      (node (ref "U6") (pin "12") (pinfunction "R1OUT_12") (pintype "output"))
    )
    (net (code "97") (name "UART_TX") (class "Default")
      (node (ref "IC1") (pin "26") (pinfunction "PA08_26") (pintype "bidirectional"))
      (node (ref "U6") (pin "11") (pinfunction "T1IN_11") (pintype "input"))
    )
    (net (code "98") (name "USB_N") (class "Default")
      (node (ref "IC1") (pin "74") (pinfunction "PA24_74") (pintype "bidirectional"))
      (node (ref "TP12") (pin "TP") (pinfunction "TP_TP") (pintype "input"))
      (node (ref "U5") (pin "IO1") (pinfunction "IO1_IO1") (pintype "bidirectional"))
      (node (ref "USB") (pin "A7") (pinfunction "DN1_A7") (pintype "bidirectional"))
      (node (ref "USB") (pin "B7") (pinfunction "DN2_B7") (pintype "bidirectional"))
    )
    (net (code "99") (name "USB_P") (class "Default")
      (node (ref "IC1") (pin "75") (pinfunction "PA25_75") (pintype "bidirectional"))
      (node (ref "TP13") (pin "TP") (pinfunction "TP_TP") (pintype "input"))
      (node (ref "U5") (pin "IO2") (pinfunction "IO2_IO2") (pintype "bidirectional"))
      (node (ref "USB") (pin "A6") (pinfunction "DP1_A6") (pintype "bidirectional"))
      (node (ref "USB") (pin "B6") (pinfunction "DP2_B6") (pintype "bidirectional"))
    )
    (net (code "100") (name "VBAT") (class "Default")
      (node (ref "C2") (pin "1") (pinfunction "1_1") (pintype "passive"))
      (node (ref "C4") (pin "1") (pinfunction "1_1") (pintype "passive"))
      (node (ref "L1") (pin "P$1") (pinfunction "1_P$1") (pintype "passive"))
      (node (ref "R13") (pin "1") (pinfunction "1_1") (pintype "passive"))
      (node (ref "R8") (pin "2") (pinfunction "2_2") (pintype "passive"))
      (node (ref "T1") (pin "E") (pinfunction "E_E") (pintype "passive"))
      (node (ref "TP2") (pin "TP") (pinfunction "TP_TP") (pintype "input"))
      (node (ref "U2") (pin "8") (pinfunction "VBAT_8") (pintype "input"))
      (node (ref "U3") (pin "P$1") (pinfunction "VOUT1_P$1") (pintype "bidirectional"))
      (node (ref "U3") (pin "P$20") (pinfunction "VOUT2_P$20") (pintype "bidirectional"))
    )
    (net (code "101") (name "VBUS") (class "Default")
      (node (ref "C1") (pin "1") (pinfunction "1_1") (pintype "passive"))
      (node (ref "LED2") (pin "A") (pinfunction "A_A") (pintype "passive"))
      (node (ref "LED3") (pin "A") (pinfunction "A_A") (pintype "passive"))
      (node (ref "R9") (pin "2") (pinfunction "2_2") (pintype "passive"))
      (node (ref "TP1") (pin "TP") (pinfunction "TP_TP") (pintype "input"))
      (node (ref "U3") (pin "P$17") (pinfunction "CE_P$17") (pintype "bidirectional"))
      (node (ref "U3") (pin "P$18") (pinfunction "VIN1_P$18") (pintype "bidirectional"))
      (node (ref "U3") (pin "P$19") (pinfunction "VIN2_P$19") (pintype "bidirectional"))
      (node (ref "U3") (pin "P$3") (pinfunction "SEL_P$3") (pintype "bidirectional"))
      (node (ref "U3") (pin "P$4") (pinfunction "PROG2_P$4") (pintype "bidirectional"))
      (node (ref "U3") (pin "P$9") (pinfunction "/TE_P$9") (pintype "bidirectional"))
      (node (ref "U5") (pin "VCC") (pinfunction "VCC_VCC") (pintype "bidirectional"))
      (node (ref "USB") (pin "A4B9") (pinfunction "VBUS_A4B9") (pintype "bidirectional"))
      (node (ref "USB") (pin "B4A9") (pinfunction "VBUS_B4A9") (pintype "bidirectional"))
    )
    (net (code "102") (name "VLIPO") (class "Default")
      (node (ref "B1") (pin "2") (pinfunction "+_2") (pintype "passive"))
      (node (ref "C7") (pin "1") (pinfunction "1_1") (pintype "passive"))
      (node (ref "TP3") (pin "TP") (pinfunction "TP_TP") (pintype "input"))
      (node (ref "U3") (pin "P$14") (pinfunction "VBAT1_P$14") (pintype "bidirectional"))
      (node (ref "U3") (pin "P$15") (pinfunction "VBAT2_P$15") (pintype "bidirectional"))
      (node (ref "U3") (pin "P$16") (pinfunction "VBATSENS_P$16") (pintype "bidirectional"))
    )
    (net (code "103") (name "XL{slash}INT") (class "Default")
      (node (ref "FPC50CONN") (pin "A48") (pinfunction "48_A48") (pintype "bidirectional"))
    )
    (net (code "104") (name "XR{slash}SCL") (class "Default")
      (node (ref "FPC50CONN") (pin "A46") (pinfunction "46_A46") (pintype "bidirectional"))
    )
    (net (code "105") (name "YD{slash}SDA") (class "Default")
      (node (ref "FPC50CONN") (pin "A47") (pinfunction "47_A47") (pintype "bidirectional"))
    )
    (net (code "106") (name "YU{slash}RES") (class "Default")
      (node (ref "FPC50CONN") (pin "A49") (pinfunction "49_A49") (pintype "bidirectional"))
    )
    (net (code "107") (name "unconnected-(DE9FEMALE-PadP6)") (class "Default")
      (node (ref "DE9FEMALE") (pin "P6") (pinfunction "P6_P6") (pintype "bidirectional"))
    )
    (net (code "108") (name "unconnected-(IC1-PA02-Pad7)") (class "Default")
      (node (ref "IC1") (pin "7") (pinfunction "PA02_7") (pintype "bidirectional"))
    )
    (net (code "109") (name "unconnected-(IC1-PA03-Pad8)") (class "Default")
      (node (ref "IC1") (pin "8") (pinfunction "PA03_8") (pintype "bidirectional"))
    )
    (net (code "110") (name "unconnected-(IC1-PA04-Pad17)") (class "Default")
      (node (ref "IC1") (pin "17") (pinfunction "PA04_17") (pintype "bidirectional"))
    )
    (net (code "111") (name "unconnected-(IC1-PA05-Pad18)") (class "Default")
      (node (ref "IC1") (pin "18") (pinfunction "PA05_18") (pintype "bidirectional"))
    )
    (net (code "112") (name "unconnected-(IC1-PA06-Pad19)") (class "Default")
      (node (ref "IC1") (pin "19") (pinfunction "PA06_19") (pintype "bidirectional"))
    )
    (net (code "113") (name "unconnected-(IC1-PA07-Pad20)") (class "Default")
      (node (ref "IC1") (pin "20") (pinfunction "PA07_20") (pintype "bidirectional"))
    )
    (net (code "114") (name "unconnected-(IC1-PA14-Pad48)") (class "Default")
      (node (ref "IC1") (pin "48") (pinfunction "PA14_48") (pintype "bidirectional"))
    )
    (net (code "115") (name "unconnected-(IC1-PA15-Pad49)") (class "Default")
      (node (ref "IC1") (pin "49") (pinfunction "PA15_49") (pintype "bidirectional"))
    )
    (net (code "116") (name "unconnected-(IC1-PA16-Pad52)") (class "Default")
      (node (ref "IC1") (pin "52") (pinfunction "PA16_52") (pintype "bidirectional"))
    )
    (net (code "117") (name "unconnected-(IC1-PA17-Pad53)") (class "Default")
      (node (ref "IC1") (pin "53") (pinfunction "PA17_53") (pintype "bidirectional"))
    )
    (net (code "118") (name "unconnected-(IC1-PA18-Pad54)") (class "Default")
      (node (ref "IC1") (pin "54") (pinfunction "PA18_54") (pintype "bidirectional"))
    )
    (net (code "119") (name "unconnected-(IC1-PA19-Pad55)") (class "Default")
      (node (ref "IC1") (pin "55") (pinfunction "PA19_55") (pintype "bidirectional"))
    )
    (net (code "120") (name "unconnected-(IC1-PA20-Pad70)") (class "Default")
      (node (ref "IC1") (pin "70") (pinfunction "PA20_70") (pintype "bidirectional"))
    )
    (net (code "121") (name "unconnected-(IC1-PA21-Pad71)") (class "Default")
      (node (ref "IC1") (pin "71") (pinfunction "PA21_71") (pintype "bidirectional"))
    )
    (net (code "122") (name "unconnected-(IC1-PA22-Pad72)") (class "Default")
      (node (ref "IC1") (pin "72") (pinfunction "PA22_72") (pintype "bidirectional"))
    )
    (net (code "123") (name "unconnected-(IC1-PA23-Pad73)") (class "Default")
      (node (ref "IC1") (pin "73") (pinfunction "PA23_73") (pintype "bidirectional"))
    )
    (net (code "124") (name "unconnected-(IC1-PA27-Pad87)") (class "Default")
      (node (ref "IC1") (pin "87") (pinfunction "PA27_87") (pintype "bidirectional"))
    )
    (net (code "125") (name "unconnected-(IC1-PB18-Pad66)") (class "Default")
      (node (ref "IC1") (pin "66") (pinfunction "PB18_66") (pintype "bidirectional"))
    )
    (net (code "126") (name "unconnected-(IC1-PB19-Pad67)") (class "Default")
      (node (ref "IC1") (pin "67") (pinfunction "PB19_67") (pintype "bidirectional"))
    )
    (net (code "127") (name "unconnected-(IC1-PB20-Pad68)") (class "Default")
      (node (ref "IC1") (pin "68") (pinfunction "PB20_68") (pintype "bidirectional"))
    )
    (net (code "128") (name "unconnected-(IC1-PB21-Pad69)") (class "Default")
      (node (ref "IC1") (pin "69") (pinfunction "PB21_69") (pintype "bidirectional"))
    )
    (net (code "129") (name "unconnected-(IC1-PB24-Pad80)") (class "Default")
      (node (ref "IC1") (pin "80") (pinfunction "PB24_80") (pintype "bidirectional"))
    )
    (net (code "130") (name "unconnected-(IC1-PC00-Pad3)") (class "Default")
      (node (ref "IC1") (pin "3") (pinfunction "PC00_3") (pintype "bidirectional"))
    )
    (net (code "131") (name "unconnected-(IC1-PC01-Pad4)") (class "Default")
      (node (ref "IC1") (pin "4") (pinfunction "PC01_4") (pintype "bidirectional"))
    )
    (net (code "132") (name "unconnected-(IC1-PC24-Pad82)") (class "Default")
      (node (ref "IC1") (pin "82") (pinfunction "PC24_82") (pintype "bidirectional"))
    )
    (net (code "133") (name "unconnected-(IC1-PC25-Pad83)") (class "Default")
      (node (ref "IC1") (pin "83") (pinfunction "PC25_83") (pintype "bidirectional"))
    )
    (net (code "134") (name "unconnected-(IC1-PC26-Pad84)") (class "Default")
      (node (ref "IC1") (pin "84") (pinfunction "PC26_84") (pintype "bidirectional"))
    )
    (net (code "135") (name "unconnected-(IC1-PC27-Pad85)") (class "Default")
      (node (ref "IC1") (pin "85") (pinfunction "PC27_85") (pintype "bidirectional"))
    )
    (net (code "136") (name "unconnected-(IC1-PC28-Pad86)") (class "Default")
      (node (ref "IC1") (pin "86") (pinfunction "PC28_86") (pintype "bidirectional"))
    )
    (net (code "137") (name "unconnected-(IC1-PN25-Pad81)") (class "Default")
      (node (ref "IC1") (pin "81") (pinfunction "PN25_81") (pintype "bidirectional"))
    )
    (net (code "138") (name "unconnected-(TAG-CONNECT-PIN3-PadP$3)") (class "Default")
      (node (ref "TAG-CONNECT") (pin "P$3") (pinfunction "PIN3_P$3") (pintype "bidirectional"))
    )
    (net (code "139") (name "unconnected-(TAG-CONNECT-PIN6-PadP$6)") (class "Default")
      (node (ref "TAG-CONNECT") (pin "P$6") (pinfunction "PIN6_P$6") (pintype "bidirectional"))
    )
    (net (code "140") (name "unconnected-(TAG-CONNECT-PIN7-PadP$7)") (class "Default")
      (node (ref "TAG-CONNECT") (pin "P$7") (pinfunction "PIN7_P$7") (pintype "bidirectional"))
    )
    (net (code "141") (name "unconnected-(TAG-CONNECT-PIN8-PadP$8)") (class "Default")
      (node (ref "TAG-CONNECT") (pin "P$8") (pinfunction "PIN8_P$8") (pintype "bidirectional"))
    )
    (net (code "142") (name "unconnected-(TAG-CONNECT-PIN9-PadP$9)") (class "Default")
      (node (ref "TAG-CONNECT") (pin "P$9") (pinfunction "PIN9_P$9") (pintype "bidirectional"))
    )
    (net (code "143") (name "unconnected-(U$5-CASE-PadCASE1)") (class "Default")
      (node (ref "U$5") (pin "CASE1") (pinfunction "CASE_CASE1") (pintype "no_connect"))
    )
    (net (code "144") (name "unconnected-(U$5-CASE-PadCASE2)") (class "Default")
      (node (ref "U$5") (pin "CASE2") (pinfunction "CASE_CASE2") (pintype "no_connect"))
    )
    (net (code "145") (name "unconnected-(U$5-PadP$3)") (class "Default")
      (node (ref "U$5") (pin "P$3") (pinfunction "P$3_P$3") (pintype "bidirectional"))
    )
    (net (code "146") (name "unconnected-(U$30-PadP3)") (class "Default")
      (node (ref "U$30") (pin "P3") (pinfunction "P3_P3") (pintype "bidirectional"))
    )
    (net (code "147") (name "unconnected-(U$30-PadP5)") (class "Default")
      (node (ref "U$30") (pin "P5") (pinfunction "P5_P5") (pintype "bidirectional"))
    )
    (net (code "148") (name "unconnected-(U$30-PadP7)") (class "Default")
      (node (ref "U$30") (pin "P7") (pinfunction "P7_P7") (pintype "bidirectional"))
    )
    (net (code "149") (name "unconnected-(U$30-PadP11)") (class "Default")
      (node (ref "U$30") (pin "P11") (pinfunction "P11_P11") (pintype "bidirectional"))
    )
    (net (code "150") (name "unconnected-(U$30-PadP12)") (class "Default")
      (node (ref "U$30") (pin "P12") (pinfunction "P12_P12") (pintype "bidirectional"))
    )
    (net (code "151") (name "unconnected-(U$30-PadP13)") (class "Default")
      (node (ref "U$30") (pin "P13") (pinfunction "P13_P13") (pintype "bidirectional"))
    )
    (net (code "152") (name "unconnected-(U$30-PadP15)") (class "Default")
      (node (ref "U$30") (pin "P15") (pinfunction "P15_P15") (pintype "bidirectional"))
    )
    (net (code "153") (name "unconnected-(U$30-PadP16)") (class "Default")
      (node (ref "U$30") (pin "P16") (pinfunction "P16_P16") (pintype "bidirectional"))
    )
    (net (code "154") (name "unconnected-(U$30-PadP17)") (class "Default")
      (node (ref "U$30") (pin "P17") (pinfunction "P17_P17") (pintype "bidirectional"))
    )
    (net (code "155") (name "unconnected-(U$30-PadP18)") (class "Default")
      (node (ref "U$30") (pin "P18") (pinfunction "P18_P18") (pintype "bidirectional"))
    )
    (net (code "156") (name "unconnected-(U$30-PadP19)") (class "Default")
      (node (ref "U$30") (pin "P19") (pinfunction "P19_P19") (pintype "bidirectional"))
    )
    (net (code "157") (name "unconnected-(U$30-PadP20)") (class "Default")
      (node (ref "U$30") (pin "P20") (pinfunction "P20_P20") (pintype "bidirectional"))
    )
    (net (code "158") (name "unconnected-(U$30-PadP21)") (class "Default")
      (node (ref "U$30") (pin "P21") (pinfunction "P21_P21") (pintype "bidirectional"))
    )
    (net (code "159") (name "unconnected-(U$30-PadP22)") (class "Default")
      (node (ref "U$30") (pin "P22") (pinfunction "P22_P22") (pintype "bidirectional"))
    )
    (net (code "160") (name "unconnected-(U$30-PadP23)") (class "Default")
      (node (ref "U$30") (pin "P23") (pinfunction "P23_P23") (pintype "bidirectional"))
    )
    (net (code "161") (name "unconnected-(U$30-PadP24)") (class "Default")
      (node (ref "U$30") (pin "P24") (pinfunction "P24_P24") (pintype "bidirectional"))
    )
    (net (code "162") (name "unconnected-(U$30-PadP26)") (class "Default")
      (node (ref "U$30") (pin "P26") (pinfunction "P26_P26") (pintype "bidirectional"))
    )
    (net (code "163") (name "unconnected-(U$30-PadP27)") (class "Default")
      (node (ref "U$30") (pin "P27") (pinfunction "P27_P27") (pintype "bidirectional"))
    )
    (net (code "164") (name "unconnected-(U$30-PadP28)") (class "Default")
      (node (ref "U$30") (pin "P28") (pinfunction "P28_P28") (pintype "bidirectional"))
    )
    (net (code "165") (name "unconnected-(U$30-PadP29)") (class "Default")
      (node (ref "U$30") (pin "P29") (pinfunction "P29_P29") (pintype "bidirectional"))
    )
    (net (code "166") (name "unconnected-(U$30-PadP31)") (class "Default")
      (node (ref "U$30") (pin "P31") (pinfunction "P31_P31") (pintype "bidirectional"))
    )
    (net (code "167") (name "unconnected-(U$30-PadP32)") (class "Default")
      (node (ref "U$30") (pin "P32") (pinfunction "P32_P32") (pintype "bidirectional"))
    )
    (net (code "168") (name "unconnected-(U$30-PadP33)") (class "Default")
      (node (ref "U$30") (pin "P33") (pinfunction "P33_P33") (pintype "bidirectional"))
    )
    (net (code "169") (name "unconnected-(U$30-PadP35)") (class "Default")
      (node (ref "U$30") (pin "P35") (pinfunction "P35_P35") (pintype "bidirectional"))
    )
    (net (code "170") (name "unconnected-(U$30-PadP36)") (class "Default")
      (node (ref "U$30") (pin "P36") (pinfunction "P36_P36") (pintype "bidirectional"))
    )
    (net (code "171") (name "unconnected-(U$30-PadP37)") (class "Default")
      (node (ref "U$30") (pin "P37") (pinfunction "P37_P37") (pintype "bidirectional"))
    )
    (net (code "172") (name "unconnected-(U$30-PadP38)") (class "Default")
      (node (ref "U$30") (pin "P38") (pinfunction "P38_P38") (pintype "bidirectional"))
    )
    (net (code "173") (name "unconnected-(U$30-PadP40)") (class "Default")
      (node (ref "U$30") (pin "P40") (pinfunction "P40_P40") (pintype "bidirectional"))
    )
    (net (code "174") (name "unconnected-(U3-{slash}PG-PadP$6)") (class "Default")
      (node (ref "U3") (pin "P$6") (pinfunction "/PG_P$6") (pintype "bidirectional"))
    )
    (net (code "175") (name "unconnected-(U5-PadGND)") (class "Default")
      (node (ref "U5") (pin "GND") (pinfunction "GND_GND") (pintype "bidirectional"))
    )
    (net (code "176") (name "unconnected-(USB-SBU1-PadA8)") (class "Default")
      (node (ref "USB") (pin "A8") (pinfunction "SBU1_A8") (pintype "bidirectional"))
    )
    (net (code "177") (name "unconnected-(USB-SBU2-PadB8)") (class "Default")
      (node (ref "USB") (pin "B8") (pinfunction "SBU2_B8") (pintype "bidirectional"))
    )
    (net (code "178") (name "unconnected-(X2G-S-Pad6)") (class "Default")
      (node (ref "X2") (pin "6") (pinfunction "S_6") (pintype "passive"))
    )
    (net (code "179") (name "unconnected-(X2H-S-Pad7)") (class "Default")
      (node (ref "X2") (pin "7") (pinfunction "S_7") (pintype "passive"))
    )
    (net (code "180") (name "unconnected-(X2I-S-Pad8)") (class "Default")
      (node (ref "X2") (pin "8") (pinfunction "S_8") (pintype "passive"))
    )
  )
)
